# VALVEBOARD_ValveDrive1.net
KiCad netlist of a schematic drawn in Altium Designer
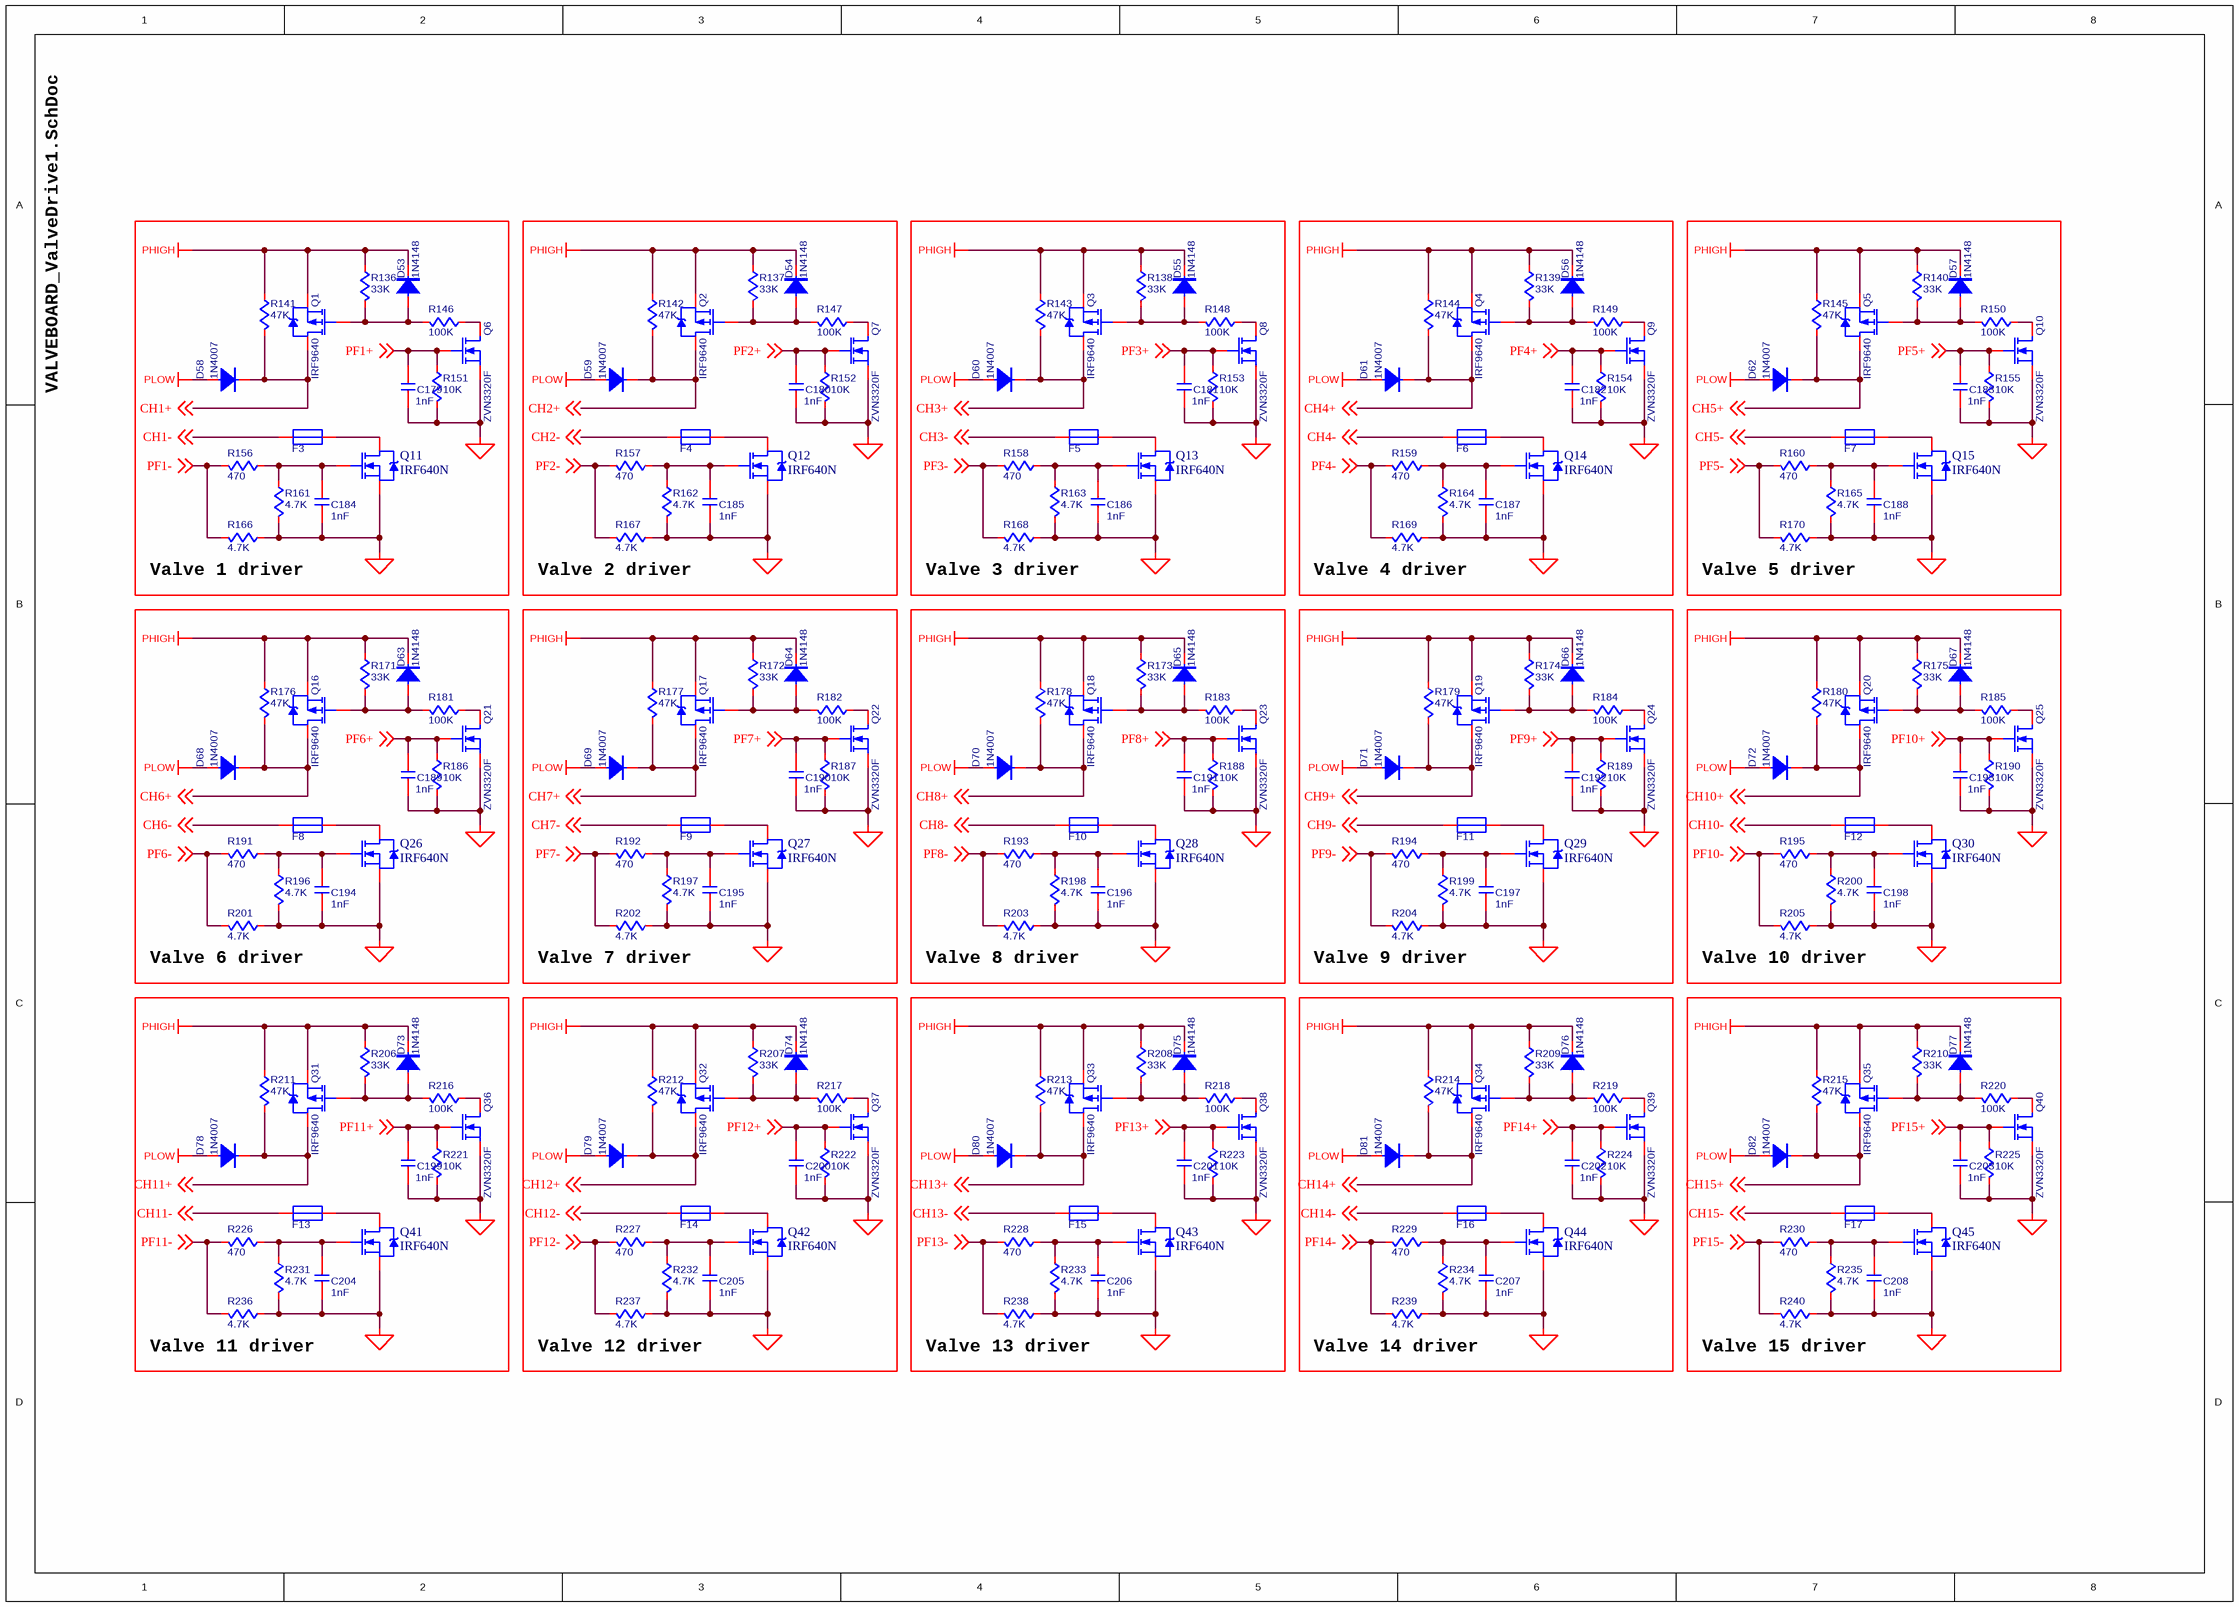
[diagram p0: VALVEBOARD_ValveDrive1.SchDoc]

(export (version "E")
  (design (tool "Eeschema 10.0.6"))
  (components
    (comp (ref "C179")
      (value "1nF")
      (footprint "zynq:C0603")
      (fields (field (name "VOLTAGE") "25V") (field (name "Comment") "C-NOMO"))
      (libsource (lib "zynq") (part "C-NOMO"))
    )
    (comp (ref "C180")
      (value "1nF")
      (footprint "zynq:C0603")
      (fields (field (name "VOLTAGE") "25V") (field (name "Comment") "C-NOMO"))
      (libsource (lib "zynq") (part "C-NOMO"))
    )
    (comp (ref "C181")
      (value "1nF")
      (footprint "zynq:C0603")
      (fields (field (name "VOLTAGE") "25V") (field (name "Comment") "C-NOMO"))
      (libsource (lib "zynq") (part "C-NOMO"))
    )
    (comp (ref "C182")
      (value "1nF")
      (footprint "zynq:C0603")
      (fields (field (name "VOLTAGE") "25V") (field (name "Comment") "C-NOMO"))
      (libsource (lib "zynq") (part "C-NOMO"))
    )
    (comp (ref "C183")
      (value "1nF")
      (footprint "zynq:C0603")
      (fields (field (name "VOLTAGE") "25V") (field (name "Comment") "C-NOMO"))
      (libsource (lib "zynq") (part "C-NOMO"))
    )
    (comp (ref "C184")
      (value "1nF")
      (footprint "zynq:C0603")
      (fields (field (name "VOLTAGE") "25V") (field (name "Comment") "C-NOMO"))
      (libsource (lib "zynq") (part "C-NOMO"))
    )
    (comp (ref "C185")
      (value "1nF")
      (footprint "zynq:C0603")
      (fields (field (name "VOLTAGE") "25V") (field (name "Comment") "C-NOMO"))
      (libsource (lib "zynq") (part "C-NOMO"))
    )
    (comp (ref "C186")
      (value "1nF")
      (footprint "zynq:C0603")
      (fields (field (name "VOLTAGE") "25V") (field (name "Comment") "C-NOMO"))
      (libsource (lib "zynq") (part "C-NOMO"))
    )
    (comp (ref "C187")
      (value "1nF")
      (footprint "zynq:C0603")
      (fields (field (name "VOLTAGE") "25V") (field (name "Comment") "C-NOMO"))
      (libsource (lib "zynq") (part "C-NOMO"))
    )
    (comp (ref "C188")
      (value "1nF")
      (footprint "zynq:C0603")
      (fields (field (name "VOLTAGE") "25V") (field (name "Comment") "C-NOMO"))
      (libsource (lib "zynq") (part "C-NOMO"))
    )
    (comp (ref "C189")
      (value "1nF")
      (footprint "zynq:C0603")
      (fields (field (name "VOLTAGE") "25V") (field (name "Comment") "C-NOMO"))
      (libsource (lib "zynq") (part "C-NOMO"))
    )
    (comp (ref "C190")
      (value "1nF")
      (footprint "zynq:C0603")
      (fields (field (name "VOLTAGE") "25V") (field (name "Comment") "C-NOMO"))
      (libsource (lib "zynq") (part "C-NOMO"))
    )
    (comp (ref "C191")
      (value "1nF")
      (footprint "zynq:C0603")
      (fields (field (name "VOLTAGE") "25V") (field (name "Comment") "C-NOMO"))
      (libsource (lib "zynq") (part "C-NOMO"))
    )
    (comp (ref "C192")
      (value "1nF")
      (footprint "zynq:C0603")
      (fields (field (name "VOLTAGE") "25V") (field (name "Comment") "C-NOMO"))
      (libsource (lib "zynq") (part "C-NOMO"))
    )
    (comp (ref "C193")
      (value "1nF")
      (footprint "zynq:C0603")
      (fields (field (name "VOLTAGE") "25V") (field (name "Comment") "C-NOMO"))
      (libsource (lib "zynq") (part "C-NOMO"))
    )
    (comp (ref "C194")
      (value "1nF")
      (footprint "zynq:C0603")
      (fields (field (name "VOLTAGE") "25V") (field (name "Comment") "C-NOMO"))
      (libsource (lib "zynq") (part "C-NOMO"))
    )
    (comp (ref "C195")
      (value "1nF")
      (footprint "zynq:C0603")
      (fields (field (name "VOLTAGE") "25V") (field (name "Comment") "C-NOMO"))
      (libsource (lib "zynq") (part "C-NOMO"))
    )
    (comp (ref "C196")
      (value "1nF")
      (footprint "zynq:C0603")
      (fields (field (name "VOLTAGE") "25V") (field (name "Comment") "C-NOMO"))
      (libsource (lib "zynq") (part "C-NOMO"))
    )
    (comp (ref "C197")
      (value "1nF")
      (footprint "zynq:C0603")
      (fields (field (name "VOLTAGE") "25V") (field (name "Comment") "C-NOMO"))
      (libsource (lib "zynq") (part "C-NOMO"))
    )
    (comp (ref "C198")
      (value "1nF")
      (footprint "zynq:C0603")
      (fields (field (name "VOLTAGE") "25V") (field (name "Comment") "C-NOMO"))
      (libsource (lib "zynq") (part "C-NOMO"))
    )
    (comp (ref "C199")
      (value "1nF")
      (footprint "zynq:C0603")
      (fields (field (name "VOLTAGE") "25V") (field (name "Comment") "C-NOMO"))
      (libsource (lib "zynq") (part "C-NOMO"))
    )
    (comp (ref "C200")
      (value "1nF")
      (footprint "zynq:C0603")
      (fields (field (name "VOLTAGE") "25V") (field (name "Comment") "C-NOMO"))
      (libsource (lib "zynq") (part "C-NOMO"))
    )
    (comp (ref "C201")
      (value "1nF")
      (footprint "zynq:C0603")
      (fields (field (name "VOLTAGE") "25V") (field (name "Comment") "C-NOMO"))
      (libsource (lib "zynq") (part "C-NOMO"))
    )
    (comp (ref "C202")
      (value "1nF")
      (footprint "zynq:C0603")
      (fields (field (name "VOLTAGE") "25V") (field (name "Comment") "C-NOMO"))
      (libsource (lib "zynq") (part "C-NOMO"))
    )
    (comp (ref "C203")
      (value "1nF")
      (footprint "zynq:C0603")
      (fields (field (name "VOLTAGE") "25V") (field (name "Comment") "C-NOMO"))
      (libsource (lib "zynq") (part "C-NOMO"))
    )
    (comp (ref "C204")
      (value "1nF")
      (footprint "zynq:C0603")
      (fields (field (name "VOLTAGE") "25V") (field (name "Comment") "C-NOMO"))
      (libsource (lib "zynq") (part "C-NOMO"))
    )
    (comp (ref "C205")
      (value "1nF")
      (footprint "zynq:C0603")
      (fields (field (name "VOLTAGE") "25V") (field (name "Comment") "C-NOMO"))
      (libsource (lib "zynq") (part "C-NOMO"))
    )
    (comp (ref "C206")
      (value "1nF")
      (footprint "zynq:C0603")
      (fields (field (name "VOLTAGE") "25V") (field (name "Comment") "C-NOMO"))
      (libsource (lib "zynq") (part "C-NOMO"))
    )
    (comp (ref "C207")
      (value "1nF")
      (footprint "zynq:C0603")
      (fields (field (name "VOLTAGE") "25V") (field (name "Comment") "C-NOMO"))
      (libsource (lib "zynq") (part "C-NOMO"))
    )
    (comp (ref "C208")
      (value "1nF")
      (footprint "zynq:C0603")
      (fields (field (name "VOLTAGE") "25V") (field (name "Comment") "C-NOMO"))
      (libsource (lib "zynq") (part "C-NOMO"))
    )
    (comp (ref "D53") (value "1N4148") (footprint "sod-123") (libsource (lib "zynq") (part "DIOD1")))
    (comp (ref "D54") (value "1N4148") (footprint "sod-123") (libsource (lib "zynq") (part "DIOD1")))
    (comp (ref "D55") (value "1N4148") (footprint "sod-123") (libsource (lib "zynq") (part "DIOD1")))
    (comp (ref "D56") (value "1N4148") (footprint "sod-123") (libsource (lib "zynq") (part "DIOD1")))
    (comp (ref "D57") (value "1N4148") (footprint "sod-123") (libsource (lib "zynq") (part "DIOD1")))
    (comp (ref "D58") (value "1N4007") (footprint "zynq:1N4148") (libsource (lib "") (part "DIOD1_1")))
    (comp (ref "D59") (value "1N4007") (footprint "zynq:1N4148") (libsource (lib "") (part "DIOD1_1")))
    (comp (ref "D60") (value "1N4007") (footprint "zynq:1N4148") (libsource (lib "") (part "DIOD1_1")))
    (comp (ref "D61") (value "1N4007") (footprint "zynq:1N4148") (libsource (lib "") (part "DIOD1_1")))
    (comp (ref "D62") (value "1N4007") (footprint "zynq:1N4148") (libsource (lib "") (part "DIOD1_1")))
    (comp (ref "D63") (value "1N4148") (footprint "sod-123") (libsource (lib "zynq") (part "DIOD1")))
    (comp (ref "D64") (value "1N4148") (footprint "sod-123") (libsource (lib "zynq") (part "DIOD1")))
    (comp (ref "D65") (value "1N4148") (footprint "sod-123") (libsource (lib "zynq") (part "DIOD1")))
    (comp (ref "D66") (value "1N4148") (footprint "sod-123") (libsource (lib "zynq") (part "DIOD1")))
    (comp (ref "D67") (value "1N4148") (footprint "sod-123") (libsource (lib "zynq") (part "DIOD1")))
    (comp (ref "D68") (value "1N4007") (footprint "zynq:1N4148") (libsource (lib "") (part "DIOD1_1")))
    (comp (ref "D69") (value "1N4007") (footprint "zynq:1N4148") (libsource (lib "") (part "DIOD1_1")))
    (comp (ref "D70") (value "1N4007") (footprint "zynq:1N4148") (libsource (lib "") (part "DIOD1_1")))
    (comp (ref "D71") (value "1N4007") (footprint "zynq:1N4148") (libsource (lib "") (part "DIOD1_1")))
    (comp (ref "D72") (value "1N4007") (footprint "zynq:1N4148") (libsource (lib "") (part "DIOD1_1")))
    (comp (ref "D73") (value "1N4148") (footprint "sod-123") (libsource (lib "zynq") (part "DIOD1")))
    (comp (ref "D74") (value "1N4148") (footprint "sod-123") (libsource (lib "zynq") (part "DIOD1")))
    (comp (ref "D75") (value "1N4148") (footprint "sod-123") (libsource (lib "zynq") (part "DIOD1")))
    (comp (ref "D76") (value "1N4148") (footprint "sod-123") (libsource (lib "zynq") (part "DIOD1")))
    (comp (ref "D77") (value "1N4148") (footprint "sod-123") (libsource (lib "zynq") (part "DIOD1")))
    (comp (ref "D78") (value "1N4007") (footprint "zynq:1N4148") (libsource (lib "") (part "DIOD1_1")))
    (comp (ref "D79") (value "1N4007") (footprint "zynq:1N4148") (libsource (lib "") (part "DIOD1_1")))
    (comp (ref "D80") (value "1N4007") (footprint "zynq:1N4148") (libsource (lib "") (part "DIOD1_1")))
    (comp (ref "D81") (value "1N4007") (footprint "zynq:1N4148") (libsource (lib "") (part "DIOD1_1")))
    (comp (ref "D82") (value "1N4007") (footprint "zynq:1N4148") (libsource (lib "") (part "DIOD1_1")))
    (comp (ref "F3") (value "F50") (footprint "zynq:F-TH") (libsource (lib "zynq") (part "F50")))
    (comp (ref "F4") (value "F50") (footprint "zynq:F-TH") (libsource (lib "zynq") (part "F50")))
    (comp (ref "F5") (value "F50") (footprint "zynq:F-TH") (libsource (lib "zynq") (part "F50")))
    (comp (ref "F6") (value "F50") (footprint "zynq:F-TH") (libsource (lib "zynq") (part "F50")))
    (comp (ref "F7") (value "F50") (footprint "zynq:F-TH") (libsource (lib "zynq") (part "F50")))
    (comp (ref "F8") (value "F50") (footprint "zynq:F-TH") (libsource (lib "zynq") (part "F50")))
    (comp (ref "F9") (value "F50") (footprint "zynq:F-TH") (libsource (lib "zynq") (part "F50")))
    (comp (ref "F10") (value "F50") (footprint "zynq:F-TH") (libsource (lib "zynq") (part "F50")))
    (comp (ref "F11") (value "F50") (footprint "zynq:F-TH") (libsource (lib "zynq") (part "F50")))
    (comp (ref "F12") (value "F50") (footprint "zynq:F-TH") (libsource (lib "zynq") (part "F50")))
    (comp (ref "F13") (value "F50") (footprint "zynq:F-TH") (libsource (lib "zynq") (part "F50")))
    (comp (ref "F14") (value "F50") (footprint "zynq:F-TH") (libsource (lib "zynq") (part "F50")))
    (comp (ref "F15") (value "F50") (footprint "zynq:F-TH") (libsource (lib "zynq") (part "F50")))
    (comp (ref "F16") (value "F50") (footprint "zynq:F-TH") (libsource (lib "zynq") (part "F50")))
    (comp (ref "F17") (value "F50") (footprint "zynq:F-TH") (libsource (lib "zynq") (part "F50")))
    (comp (ref "Q1")
      (value "IRF9640")
      (footprint "TO-220AB")
      (description "P-Channel Power MOSFET")
      (fields (field (name "PUBLISHER") "Altium Limited"))
      (libsource (lib "zynq") (part "IRF9640"))
    )
    (comp (ref "Q2")
      (value "IRF9640")
      (footprint "TO-220AB")
      (description "P-Channel Power MOSFET")
      (fields (field (name "PUBLISHER") "Altium Limited"))
      (libsource (lib "zynq") (part "IRF9640"))
    )
    (comp (ref "Q3")
      (value "IRF9640")
      (footprint "TO-220AB")
      (description "P-Channel Power MOSFET")
      (fields (field (name "PUBLISHER") "Altium Limited"))
      (libsource (lib "zynq") (part "IRF9640"))
    )
    (comp (ref "Q4")
      (value "IRF9640")
      (footprint "TO-220AB")
      (description "P-Channel Power MOSFET")
      (fields (field (name "PUBLISHER") "Altium Limited"))
      (libsource (lib "zynq") (part "IRF9640"))
    )
    (comp (ref "Q5")
      (value "IRF9640")
      (footprint "TO-220AB")
      (description "P-Channel Power MOSFET")
      (fields (field (name "PUBLISHER") "Altium Limited"))
      (libsource (lib "zynq") (part "IRF9640"))
    )
    (comp (ref "Q6")
      (value "ZVN3320F")
      (footprint "zynq:ZVN3320F")
      (description "N-Channel MOSFET")
      (fields (field (name "PUBLISHER") "Altium Limited"))
      (libsource (lib "zynq") (part "ZVN3320F"))
    )
    (comp (ref "Q7")
      (value "ZVN3320F")
      (footprint "zynq:ZVN3320F")
      (description "N-Channel MOSFET")
      (fields (field (name "PUBLISHER") "Altium Limited"))
      (libsource (lib "zynq") (part "ZVN3320F"))
    )
    (comp (ref "Q8")
      (value "ZVN3320F")
      (footprint "zynq:ZVN3320F")
      (description "N-Channel MOSFET")
      (fields (field (name "PUBLISHER") "Altium Limited"))
      (libsource (lib "zynq") (part "ZVN3320F"))
    )
    (comp (ref "Q9")
      (value "ZVN3320F")
      (footprint "zynq:ZVN3320F")
      (description "N-Channel MOSFET")
      (fields (field (name "PUBLISHER") "Altium Limited"))
      (libsource (lib "zynq") (part "ZVN3320F"))
    )
    (comp (ref "Q10")
      (value "ZVN3320F")
      (footprint "zynq:ZVN3320F")
      (description "N-Channel MOSFET")
      (fields (field (name "PUBLISHER") "Altium Limited"))
      (libsource (lib "zynq") (part "ZVN3320F"))
    )
    (comp (ref "Q11")
      (value "IRF640N")
      (footprint "zynq:TO-220AB")
      (description "N-Channel Power MOSFET")
      (fields (field (name "PUBLISHER") "Altium Limited"))
      (libsource (lib "zynq") (part "IRF640N"))
    )
    (comp (ref "Q12")
      (value "IRF640N")
      (footprint "zynq:TO-220AB")
      (description "N-Channel Power MOSFET")
      (fields (field (name "PUBLISHER") "Altium Limited"))
      (libsource (lib "zynq") (part "IRF640N"))
    )
    (comp (ref "Q13")
      (value "IRF640N")
      (footprint "zynq:TO-220AB")
      (description "N-Channel Power MOSFET")
      (fields (field (name "PUBLISHER") "Altium Limited"))
      (libsource (lib "zynq") (part "IRF640N"))
    )
    (comp (ref "Q14")
      (value "IRF640N")
      (footprint "zynq:TO-220AB")
      (description "N-Channel Power MOSFET")
      (fields (field (name "PUBLISHER") "Altium Limited"))
      (libsource (lib "zynq") (part "IRF640N"))
    )
    (comp (ref "Q15")
      (value "IRF640N")
      (footprint "zynq:TO-220AB")
      (description "N-Channel Power MOSFET")
      (fields (field (name "PUBLISHER") "Altium Limited"))
      (libsource (lib "zynq") (part "IRF640N"))
    )
    (comp (ref "Q16")
      (value "IRF9640")
      (footprint "TO-220AB")
      (description "P-Channel Power MOSFET")
      (fields (field (name "PUBLISHER") "Altium Limited"))
      (libsource (lib "zynq") (part "IRF9640"))
    )
    (comp (ref "Q17")
      (value "IRF9640")
      (footprint "TO-220AB")
      (description "P-Channel Power MOSFET")
      (fields (field (name "PUBLISHER") "Altium Limited"))
      (libsource (lib "zynq") (part "IRF9640"))
    )
    (comp (ref "Q18")
      (value "IRF9640")
      (footprint "TO-220AB")
      (description "P-Channel Power MOSFET")
      (fields (field (name "PUBLISHER") "Altium Limited"))
      (libsource (lib "zynq") (part "IRF9640"))
    )
    (comp (ref "Q19")
      (value "IRF9640")
      (footprint "TO-220AB")
      (description "P-Channel Power MOSFET")
      (fields (field (name "PUBLISHER") "Altium Limited"))
      (libsource (lib "zynq") (part "IRF9640"))
    )
    (comp (ref "Q20")
      (value "IRF9640")
      (footprint "TO-220AB")
      (description "P-Channel Power MOSFET")
      (fields (field (name "PUBLISHER") "Altium Limited"))
      (libsource (lib "zynq") (part "IRF9640"))
    )
    (comp (ref "Q21")
      (value "ZVN3320F")
      (footprint "zynq:ZVN3320F")
      (description "N-Channel MOSFET")
      (fields (field (name "PUBLISHER") "Altium Limited"))
      (libsource (lib "zynq") (part "ZVN3320F"))
    )
    (comp (ref "Q22")
      (value "ZVN3320F")
      (footprint "zynq:ZVN3320F")
      (description "N-Channel MOSFET")
      (fields (field (name "PUBLISHER") "Altium Limited"))
      (libsource (lib "zynq") (part "ZVN3320F"))
    )
    (comp (ref "Q23")
      (value "ZVN3320F")
      (footprint "zynq:ZVN3320F")
      (description "N-Channel MOSFET")
      (fields (field (name "PUBLISHER") "Altium Limited"))
      (libsource (lib "zynq") (part "ZVN3320F"))
    )
    (comp (ref "Q24")
      (value "ZVN3320F")
      (footprint "zynq:ZVN3320F")
      (description "N-Channel MOSFET")
      (fields (field (name "PUBLISHER") "Altium Limited"))
      (libsource (lib "zynq") (part "ZVN3320F"))
    )
    (comp (ref "Q25")
      (value "ZVN3320F")
      (footprint "zynq:ZVN3320F")
      (description "N-Channel MOSFET")
      (fields (field (name "PUBLISHER") "Altium Limited"))
      (libsource (lib "zynq") (part "ZVN3320F"))
    )
    (comp (ref "Q26")
      (value "IRF640N")
      (footprint "zynq:TO-220AB")
      (description "N-Channel Power MOSFET")
      (fields (field (name "PUBLISHER") "Altium Limited"))
      (libsource (lib "zynq") (part "IRF640N"))
    )
    (comp (ref "Q27")
      (value "IRF640N")
      (footprint "zynq:TO-220AB")
      (description "N-Channel Power MOSFET")
      (fields (field (name "PUBLISHER") "Altium Limited"))
      (libsource (lib "zynq") (part "IRF640N"))
    )
    (comp (ref "Q28")
      (value "IRF640N")
      (footprint "zynq:TO-220AB")
      (description "N-Channel Power MOSFET")
      (fields (field (name "PUBLISHER") "Altium Limited"))
      (libsource (lib "zynq") (part "IRF640N"))
    )
    (comp (ref "Q29")
      (value "IRF640N")
      (footprint "zynq:TO-220AB")
      (description "N-Channel Power MOSFET")
      (fields (field (name "PUBLISHER") "Altium Limited"))
      (libsource (lib "zynq") (part "IRF640N"))
    )
    (comp (ref "Q30")
      (value "IRF640N")
      (footprint "zynq:TO-220AB")
      (description "N-Channel Power MOSFET")
      (fields (field (name "PUBLISHER") "Altium Limited"))
      (libsource (lib "zynq") (part "IRF640N"))
    )
    (comp (ref "Q31")
      (value "IRF9640")
      (footprint "TO-220AB")
      (description "P-Channel Power MOSFET")
      (fields (field (name "PUBLISHER") "Altium Limited"))
      (libsource (lib "zynq") (part "IRF9640"))
    )
    (comp (ref "Q32")
      (value "IRF9640")
      (footprint "TO-220AB")
      (description "P-Channel Power MOSFET")
      (fields (field (name "PUBLISHER") "Altium Limited"))
      (libsource (lib "zynq") (part "IRF9640"))
    )
    (comp (ref "Q33")
      (value "IRF9640")
      (footprint "TO-220AB")
      (description "P-Channel Power MOSFET")
      (fields (field (name "PUBLISHER") "Altium Limited"))
      (libsource (lib "zynq") (part "IRF9640"))
    )
    (comp (ref "Q34")
      (value "IRF9640")
      (footprint "TO-220AB")
      (description "P-Channel Power MOSFET")
      (fields (field (name "PUBLISHER") "Altium Limited"))
      (libsource (lib "zynq") (part "IRF9640"))
    )
    (comp (ref "Q35")
      (value "IRF9640")
      (footprint "TO-220AB")
      (description "P-Channel Power MOSFET")
      (fields (field (name "PUBLISHER") "Altium Limited"))
      (libsource (lib "zynq") (part "IRF9640"))
    )
    (comp (ref "Q36")
      (value "ZVN3320F")
      (footprint "zynq:ZVN3320F")
      (description "N-Channel MOSFET")
      (fields (field (name "PUBLISHER") "Altium Limited"))
      (libsource (lib "zynq") (part "ZVN3320F"))
    )
    (comp (ref "Q37")
      (value "ZVN3320F")
      (footprint "zynq:ZVN3320F")
      (description "N-Channel MOSFET")
      (fields (field (name "PUBLISHER") "Altium Limited"))
      (libsource (lib "zynq") (part "ZVN3320F"))
    )
    (comp (ref "Q38")
      (value "ZVN3320F")
      (footprint "zynq:ZVN3320F")
      (description "N-Channel MOSFET")
      (fields (field (name "PUBLISHER") "Altium Limited"))
      (libsource (lib "zynq") (part "ZVN3320F"))
    )
    (comp (ref "Q39")
      (value "ZVN3320F")
      (footprint "zynq:ZVN3320F")
      (description "N-Channel MOSFET")
      (fields (field (name "PUBLISHER") "Altium Limited"))
      (libsource (lib "zynq") (part "ZVN3320F"))
    )
    (comp (ref "Q40")
      (value "ZVN3320F")
      (footprint "zynq:ZVN3320F")
      (description "N-Channel MOSFET")
      (fields (field (name "PUBLISHER") "Altium Limited"))
      (libsource (lib "zynq") (part "ZVN3320F"))
    )
    (comp (ref "Q41")
      (value "IRF640N")
      (footprint "zynq:TO-220AB")
      (description "N-Channel Power MOSFET")
      (fields (field (name "PUBLISHER") "Altium Limited"))
      (libsource (lib "zynq") (part "IRF640N"))
    )
    (comp (ref "Q42")
      (value "IRF640N")
      (footprint "zynq:TO-220AB")
      (description "N-Channel Power MOSFET")
      (fields (field (name "PUBLISHER") "Altium Limited"))
      (libsource (lib "zynq") (part "IRF640N"))
    )
    (comp (ref "Q43")
      (value "IRF640N")
      (footprint "zynq:TO-220AB")
      (description "N-Channel Power MOSFET")
      (fields (field (name "PUBLISHER") "Altium Limited"))
      (libsource (lib "zynq") (part "IRF640N"))
    )
    (comp (ref "Q44")
      (value "IRF640N")
      (footprint "zynq:TO-220AB")
      (description "N-Channel Power MOSFET")
      (fields (field (name "PUBLISHER") "Altium Limited"))
      (libsource (lib "zynq") (part "IRF640N"))
    )
    (comp (ref "Q45")
      (value "IRF640N")
      (footprint "zynq:TO-220AB")
      (description "N-Channel Power MOSFET")
      (fields (field (name "PUBLISHER") "Altium Limited"))
      (libsource (lib "zynq") (part "IRF640N"))
    )
    (comp (ref "R136")
      (value "33K")
      (footprint "zynq:R0603")
      (fields (field (name "Comment") "R"))
      (libsource (lib "zynq") (part "R"))
    )
    (comp (ref "R137")
      (value "33K")
      (footprint "zynq:R0603")
      (fields (field (name "Comment") "R"))
      (libsource (lib "zynq") (part "R"))
    )
    (comp (ref "R138")
      (value "33K")
      (footprint "zynq:R0603")
      (fields (field (name "Comment") "R"))
      (libsource (lib "zynq") (part "R"))
    )
    (comp (ref "R139")
      (value "33K")
      (footprint "zynq:R0603")
      (fields (field (name "Comment") "R"))
      (libsource (lib "zynq") (part "R"))
    )
    (comp (ref "R140")
      (value "33K")
      (footprint "zynq:R0603")
      (fields (field (name "Comment") "R"))
      (libsource (lib "zynq") (part "R"))
    )
    (comp (ref "R141")
      (value "47K")
      (footprint "R2512")
      (fields (field (name "Comment") "R"))
      (libsource (lib "zynq") (part "R"))
    )
    (comp (ref "R142")
      (value "47K")
      (footprint "R2512")
      (fields (field (name "Comment") "R"))
      (libsource (lib "zynq") (part "R"))
    )
    (comp (ref "R143")
      (value "47K")
      (footprint "R2512")
      (fields (field (name "Comment") "R"))
      (libsource (lib "zynq") (part "R"))
    )
    (comp (ref "R144")
      (value "47K")
      (footprint "R2512")
      (fields (field (name "Comment") "R"))
      (libsource (lib "zynq") (part "R"))
    )
    (comp (ref "R145")
      (value "47K")
      (footprint "R2512")
      (fields (field (name "Comment") "R"))
      (libsource (lib "zynq") (part "R"))
    )
    (comp (ref "R146")
      (value "100K")
      (footprint "zynq:R0603")
      (fields (field (name "Comment") "R"))
      (libsource (lib "zynq") (part "R"))
    )
    (comp (ref "R147")
      (value "100K")
      (footprint "zynq:R0603")
      (fields (field (name "Comment") "R"))
      (libsource (lib "zynq") (part "R"))
    )
    (comp (ref "R148")
      (value "100K")
      (footprint "zynq:R0603")
      (fields (field (name "Comment") "R"))
      (libsource (lib "zynq") (part "R"))
    )
    (comp (ref "R149")
      (value "100K")
      (footprint "zynq:R0603")
      (fields (field (name "Comment") "R"))
      (libsource (lib "zynq") (part "R"))
    )
    (comp (ref "R150")
      (value "100K")
      (footprint "zynq:R0603")
      (fields (field (name "Comment") "R"))
      (libsource (lib "zynq") (part "R"))
    )
    (comp (ref "R151")
      (value "10K")
      (footprint "zynq:R0603")
      (fields (field (name "Comment") "R"))
      (libsource (lib "zynq") (part "R"))
    )
    (comp (ref "R152")
      (value "10K")
      (footprint "zynq:R0603")
      (fields (field (name "Comment") "R"))
      (libsource (lib "zynq") (part "R"))
    )
    (comp (ref "R153")
      (value "10K")
      (footprint "zynq:R0603")
      (fields (field (name "Comment") "R"))
      (libsource (lib "zynq") (part "R"))
    )
    (comp (ref "R154")
      (value "10K")
      (footprint "zynq:R0603")
      (fields (field (name "Comment") "R"))
      (libsource (lib "zynq") (part "R"))
    )
    (comp (ref "R155")
      (value "10K")
      (footprint "zynq:R0603")
      (fields (field (name "Comment") "R"))
      (libsource (lib "zynq") (part "R"))
    )
    (comp (ref "R156")
      (value "470")
      (footprint "zynq:R0402")
      (fields (field (name "Comment") "R"))
      (libsource (lib "zynq") (part "R"))
    )
    (comp (ref "R157")
      (value "470")
      (footprint "zynq:R0402")
      (fields (field (name "Comment") "R"))
      (libsource (lib "zynq") (part "R"))
    )
    (comp (ref "R158")
      (value "470")
      (footprint "zynq:R0402")
      (fields (field (name "Comment") "R"))
      (libsource (lib "zynq") (part "R"))
    )
    (comp (ref "R159")
      (value "470")
      (footprint "zynq:R0402")
      (fields (field (name "Comment") "R"))
      (libsource (lib "zynq") (part "R"))
    )
    (comp (ref "R160")
      (value "470")
      (footprint "zynq:R0402")
      (fields (field (name "Comment") "R"))
      (libsource (lib "zynq") (part "R"))
    )
    (comp (ref "R161")
      (value "4.7K")
      (footprint "zynq:R0402")
      (fields (field (name "Comment") "R"))
      (libsource (lib "zynq") (part "R"))
    )
    (comp (ref "R162")
      (value "4.7K")
      (footprint "zynq:R0402")
      (fields (field (name "Comment") "R"))
      (libsource (lib "zynq") (part "R"))
    )
    (comp (ref "R163")
      (value "4.7K")
      (footprint "zynq:R0402")
      (fields (field (name "Comment") "R"))
      (libsource (lib "zynq") (part "R"))
    )
    (comp (ref "R164")
      (value "4.7K")
      (footprint "zynq:R0402")
      (fields (field (name "Comment") "R"))
      (libsource (lib "zynq") (part "R"))
    )
    (comp (ref "R165")
      (value "4.7K")
      (footprint "zynq:R0402")
      (fields (field (name "Comment") "R"))
      (libsource (lib "zynq") (part "R"))
    )
    (comp (ref "R166")
      (value "4.7K")
      (footprint "zynq:R0402")
      (fields (field (name "Comment") "R"))
      (libsource (lib "zynq") (part "R"))
    )
    (comp (ref "R167")
      (value "4.7K")
      (footprint "zynq:R0402")
      (fields (field (name "Comment") "R"))
      (libsource (lib "zynq") (part "R"))
    )
    (comp (ref "R168")
      (value "4.7K")
      (footprint "zynq:R0402")
      (fields (field (name "Comment") "R"))
      (libsource (lib "zynq") (part "R"))
    )
    (comp (ref "R169")
      (value "4.7K")
      (footprint "zynq:R0402")
      (fields (field (name "Comment") "R"))
      (libsource (lib "zynq") (part "R"))
    )
    (comp (ref "R170")
      (value "4.7K")
      (footprint "zynq:R0402")
      (fields (field (name "Comment") "R"))
      (libsource (lib "zynq") (part "R"))
    )
    (comp (ref "R171")
      (value "33K")
      (footprint "zynq:R0603")
      (fields (field (name "Comment") "R"))
      (libsource (lib "zynq") (part "R"))
    )
    (comp (ref "R172")
      (value "33K")
      (footprint "zynq:R0603")
      (fields (field (name "Comment") "R"))
      (libsource (lib "zynq") (part "R"))
    )
    (comp (ref "R173")
      (value "33K")
      (footprint "zynq:R0603")
      (fields (field (name "Comment") "R"))
      (libsource (lib "zynq") (part "R"))
    )
    (comp (ref "R174")
      (value "33K")
      (footprint "zynq:R0603")
      (fields (field (name "Comment") "R"))
      (libsource (lib "zynq") (part "R"))
    )
    (comp (ref "R175")
      (value "33K")
      (footprint "zynq:R0603")
      (fields (field (name "Comment") "R"))
      (libsource (lib "zynq") (part "R"))
    )
    (comp (ref "R176")
      (value "47K")
      (footprint "R2512")
      (fields (field (name "Comment") "R"))
      (libsource (lib "zynq") (part "R"))
    )
    (comp (ref "R177")
      (value "47K")
      (footprint "R2512")
      (fields (field (name "Comment") "R"))
      (libsource (lib "zynq") (part "R"))
    )
    (comp (ref "R178")
      (value "47K")
      (footprint "R2512")
      (fields (field (name "Comment") "R"))
      (libsource (lib "zynq") (part "R"))
    )
    (comp (ref "R179")
      (value "47K")
      (footprint "R2512")
      (fields (field (name "Comment") "R"))
      (libsource (lib "zynq") (part "R"))
    )
    (comp (ref "R180")
      (value "47K")
      (footprint "R2512")
      (fields (field (name "Comment") "R"))
      (libsource (lib "zynq") (part "R"))
    )
    (comp (ref "R181")
      (value "100K")
      (footprint "zynq:R0603")
      (fields (field (name "Comment") "R"))
      (libsource (lib "zynq") (part "R"))
    )
    (comp (ref "R182")
      (value "100K")
      (footprint "zynq:R0603")
      (fields (field (name "Comment") "R"))
      (libsource (lib "zynq") (part "R"))
    )
    (comp (ref "R183")
      (value "100K")
      (footprint "zynq:R0603")
      (fields (field (name "Comment") "R"))
      (libsource (lib "zynq") (part "R"))
    )
    (comp (ref "R184")
      (value "100K")
      (footprint "zynq:R0603")
      (fields (field (name "Comment") "R"))
      (libsource (lib "zynq") (part "R"))
    )
    (comp (ref "R185")
      (value "100K")
      (footprint "zynq:R0603")
      (fields (field (name "Comment") "R"))
      (libsource (lib "zynq") (part "R"))
    )
    (comp (ref "R186")
      (value "10K")
      (footprint "zynq:R0603")
      (fields (field (name "Comment") "R"))
      (libsource (lib "zynq") (part "R"))
    )
    (comp (ref "R187")
      (value "10K")
      (footprint "zynq:R0603")
      (fields (field (name "Comment") "R"))
      (libsource (lib "zynq") (part "R"))
    )
    (comp (ref "R188")
      (value "10K")
      (footprint "zynq:R0603")
      (fields (field (name "Comment") "R"))
      (libsource (lib "zynq") (part "R"))
    )
    (comp (ref "R189")
      (value "10K")
      (footprint "zynq:R0603")
      (fields (field (name "Comment") "R"))
      (libsource (lib "zynq") (part "R"))
    )
    (comp (ref "R190")
      (value "10K")
      (footprint "zynq:R0603")
      (fields (field (name "Comment") "R"))
      (libsource (lib "zynq") (part "R"))
    )
    (comp (ref "R191")
      (value "470")
      (footprint "zynq:R0402")
      (fields (field (name "Comment") "R"))
      (libsource (lib "zynq") (part "R"))
    )
    (comp (ref "R192")
      (value "470")
      (footprint "zynq:R0402")
      (fields (field (name "Comment") "R"))
      (libsource (lib "zynq") (part "R"))
    )
    (comp (ref "R193")
      (value "470")
      (footprint "zynq:R0402")
      (fields (field (name "Comment") "R"))
      (libsource (lib "zynq") (part "R"))
    )
    (comp (ref "R194")
      (value "470")
      (footprint "zynq:R0402")
      (fields (field (name "Comment") "R"))
      (libsource (lib "zynq") (part "R"))
    )
    (comp (ref "R195")
      (value "470")
      (footprint "zynq:R0402")
      (fields (field (name "Comment") "R"))
      (libsource (lib "zynq") (part "R"))
    )
    (comp (ref "R196")
      (value "4.7K")
      (footprint "zynq:R0402")
      (fields (field (name "Comment") "R"))
      (libsource (lib "zynq") (part "R"))
    )
    (comp (ref "R197")
      (value "4.7K")
      (footprint "zynq:R0402")
      (fields (field (name "Comment") "R"))
      (libsource (lib "zynq") (part "R"))
    )
    (comp (ref "R198")
      (value "4.7K")
      (footprint "zynq:R0402")
      (fields (field (name "Comment") "R"))
      (libsource (lib "zynq") (part "R"))
    )
    (comp (ref "R199")
      (value "4.7K")
      (footprint "zynq:R0402")
      (fields (field (name "Comment") "R"))
      (libsource (lib "zynq") (part "R"))
    )
    (comp (ref "R200")
      (value "4.7K")
      (footprint "zynq:R0402")
      (fields (field (name "Comment") "R"))
      (libsource (lib "zynq") (part "R"))
    )
    (comp (ref "R201")
      (value "4.7K")
      (footprint "zynq:R0402")
      (fields (field (name "Comment") "R"))
      (libsource (lib "zynq") (part "R"))
    )
    (comp (ref "R202")
      (value "4.7K")
      (footprint "zynq:R0402")
      (fields (field (name "Comment") "R"))
      (libsource (lib "zynq") (part "R"))
    )
    (comp (ref "R203")
      (value "4.7K")
      (footprint "zynq:R0402")
      (fields (field (name "Comment") "R"))
      (libsource (lib "zynq") (part "R"))
    )
    (comp (ref "R204")
      (value "4.7K")
      (footprint "zynq:R0402")
      (fields (field (name "Comment") "R"))
      (libsource (lib "zynq") (part "R"))
    )
    (comp (ref "R205")
      (value "4.7K")
      (footprint "zynq:R0402")
      (fields (field (name "Comment") "R"))
      (libsource (lib "zynq") (part "R"))
    )
    (comp (ref "R206")
      (value "33K")
      (footprint "zynq:R0603")
      (fields (field (name "Comment") "R"))
      (libsource (lib "zynq") (part "R"))
    )
    (comp (ref "R207")
      (value "33K")
      (footprint "zynq:R0603")
      (fields (field (name "Comment") "R"))
      (libsource (lib "zynq") (part "R"))
    )
    (comp (ref "R208")
      (value "33K")
      (footprint "zynq:R0603")
      (fields (field (name "Comment") "R"))
      (libsource (lib "zynq") (part "R"))
    )
    (comp (ref "R209")
      (value "33K")
      (footprint "zynq:R0603")
      (fields (field (name "Comment") "R"))
      (libsource (lib "zynq") (part "R"))
    )
    (comp (ref "R210")
      (value "33K")
      (footprint "zynq:R0603")
      (fields (field (name "Comment") "R"))
      (libsource (lib "zynq") (part "R"))
    )
    (comp (ref "R211")
      (value "47K")
      (footprint "R2512")
      (fields (field (name "Comment") "R"))
      (libsource (lib "zynq") (part "R"))
    )
    (comp (ref "R212")
      (value "47K")
      (footprint "R2512")
      (fields (field (name "Comment") "R"))
      (libsource (lib "zynq") (part "R"))
    )
    (comp (ref "R213")
      (value "47K")
      (footprint "R2512")
      (fields (field (name "Comment") "R"))
      (libsource (lib "zynq") (part "R"))
    )
    (comp (ref "R214")
      (value "47K")
      (footprint "R2512")
      (fields (field (name "Comment") "R"))
      (libsource (lib "zynq") (part "R"))
    )
    (comp (ref "R215")
      (value "47K")
      (footprint "R2512")
      (fields (field (name "Comment") "R"))
      (libsource (lib "zynq") (part "R"))
    )
    (comp (ref "R216")
      (value "100K")
      (footprint "zynq:R0603")
      (fields (field (name "Comment") "R"))
      (libsource (lib "zynq") (part "R"))
    )
    (comp (ref "R217")
      (value "100K")
      (footprint "zynq:R0603")
      (fields (field (name "Comment") "R"))
      (libsource (lib "zynq") (part "R"))
    )
    (comp (ref "R218")
      (value "100K")
      (footprint "zynq:R0603")
      (fields (field (name "Comment") "R"))
      (libsource (lib "zynq") (part "R"))
    )
    (comp (ref "R219")
      (value "100K")
      (footprint "zynq:R0603")
      (fields (field (name "Comment") "R"))
      (libsource (lib "zynq") (part "R"))
    )
    (comp (ref "R220")
      (value "100K")
      (footprint "zynq:R0603")
      (fields (field (name "Comment") "R"))
      (libsource (lib "zynq") (part "R"))
    )
    (comp (ref "R221")
      (value "10K")
      (footprint "zynq:R0603")
      (fields (field (name "Comment") "R"))
      (libsource (lib "zynq") (part "R"))
    )
    (comp (ref "R222")
      (value "10K")
      (footprint "zynq:R0603")
      (fields (field (name "Comment") "R"))
      (libsource (lib "zynq") (part "R"))
    )
    (comp (ref "R223")
      (value "10K")
      (footprint "zynq:R0603")
      (fields (field (name "Comment") "R"))
      (libsource (lib "zynq") (part "R"))
    )
    (comp (ref "R224")
      (value "10K")
      (footprint "zynq:R0603")
      (fields (field (name "Comment") "R"))
      (libsource (lib "zynq") (part "R"))
    )
    (comp (ref "R225")
      (value "10K")
      (footprint "zynq:R0603")
      (fields (field (name "Comment") "R"))
      (libsource (lib "zynq") (part "R"))
    )
    (comp (ref "R226")
      (value "470")
      (footprint "zynq:R0402")
      (fields (field (name "Comment") "R"))
      (libsource (lib "zynq") (part "R"))
    )
    (comp (ref "R227")
      (value "470")
      (footprint "zynq:R0402")
      (fields (field (name "Comment") "R"))
      (libsource (lib "zynq") (part "R"))
    )
    (comp (ref "R228")
      (value "470")
      (footprint "zynq:R0402")
      (fields (field (name "Comment") "R"))
      (libsource (lib "zynq") (part "R"))
    )
    (comp (ref "R229")
      (value "470")
      (footprint "zynq:R0402")
      (fields (field (name "Comment") "R"))
      (libsource (lib "zynq") (part "R"))
    )
    (comp (ref "R230")
      (value "470")
      (footprint "zynq:R0402")
      (fields (field (name "Comment") "R"))
      (libsource (lib "zynq") (part "R"))
    )
    (comp (ref "R231")
      (value "4.7K")
      (footprint "zynq:R0402")
      (fields (field (name "Comment") "R"))
      (libsource (lib "zynq") (part "R"))
    )
    (comp (ref "R232")
      (value "4.7K")
      (footprint "zynq:R0402")
      (fields (field (name "Comment") "R"))
      (libsource (lib "zynq") (part "R"))
    )
    (comp (ref "R233")
      (value "4.7K")
      (footprint "zynq:R0402")
      (fields (field (name "Comment") "R"))
      (libsource (lib "zynq") (part "R"))
    )
    (comp (ref "R234")
      (value "4.7K")
      (footprint "zynq:R0402")
      (fields (field (name "Comment") "R"))
      (libsource (lib "zynq") (part "R"))
    )
    (comp (ref "R235")
      (value "4.7K")
      (footprint "zynq:R0402")
      (fields (field (name "Comment") "R"))
      (libsource (lib "zynq") (part "R"))
    )
    (comp (ref "R236")
      (value "4.7K")
      (footprint "zynq:R0402")
      (fields (field (name "Comment") "R"))
      (libsource (lib "zynq") (part "R"))
    )
    (comp (ref "R237")
      (value "4.7K")
      (footprint "zynq:R0402")
      (fields (field (name "Comment") "R"))
      (libsource (lib "zynq") (part "R"))
    )
    (comp (ref "R238")
      (value "4.7K")
      (footprint "zynq:R0402")
      (fields (field (name "Comment") "R"))
      (libsource (lib "zynq") (part "R"))
    )
    (comp (ref "R239")
      (value "4.7K")
      (footprint "zynq:R0402")
      (fields (field (name "Comment") "R"))
      (libsource (lib "zynq") (part "R"))
    )
    (comp (ref "R240")
      (value "4.7K")
      (footprint "zynq:R0402")
      (fields (field (name "Comment") "R"))
      (libsource (lib "zynq") (part "R"))
    )
  )
  (nets
    (net (code "1") (name "CH1+") (class "Default")
      (node (ref "D58") (pin "1") (pinfunction "1_1") (pintype "passive"))
      (node (ref "Q1") (pin "2") (pinfunction "D_2") (pintype "passive"))
      (node (ref "R141") (pin "1") (pinfunction "1_1") (pintype "passive"))
    )
    (net (code "2") (name "CH1-") (class "Default") (node (ref "F3") (pin "1") (pintype "passive")))
    (net (code "3") (name "CH2+") (class "Default")
      (node (ref "D59") (pin "1") (pinfunction "1_1") (pintype "passive"))
      (node (ref "Q2") (pin "2") (pinfunction "D_2") (pintype "passive"))
      (node (ref "R142") (pin "1") (pinfunction "1_1") (pintype "passive"))
    )
    (net (code "4") (name "CH2-") (class "Default") (node (ref "F4") (pin "1") (pintype "passive")))
    (net (code "5") (name "CH3+") (class "Default")
      (node (ref "D60") (pin "1") (pinfunction "1_1") (pintype "passive"))
      (node (ref "Q3") (pin "2") (pinfunction "D_2") (pintype "passive"))
      (node (ref "R143") (pin "1") (pinfunction "1_1") (pintype "passive"))
    )
    (net (code "6") (name "CH3-") (class "Default") (node (ref "F5") (pin "1") (pintype "passive")))
    (net (code "7") (name "CH4+") (class "Default")
      (node (ref "D61") (pin "1") (pinfunction "1_1") (pintype "passive"))
      (node (ref "Q4") (pin "2") (pinfunction "D_2") (pintype "passive"))
      (node (ref "R144") (pin "1") (pinfunction "1_1") (pintype "passive"))
    )
    (net (code "8") (name "CH4-") (class "Default") (node (ref "F6") (pin "1") (pintype "passive")))
    (net (code "9") (name "CH5+") (class "Default")
      (node (ref "D62") (pin "1") (pinfunction "1_1") (pintype "passive"))
      (node (ref "Q5") (pin "2") (pinfunction "D_2") (pintype "passive"))
      (node (ref "R145") (pin "1") (pinfunction "1_1") (pintype "passive"))
    )
    (net (code "10") (name "CH5-") (class "Default") (node (ref "F7") (pin "1") (pintype "passive")))
    (net (code "11") (name "CH6+") (class "Default")
      (node (ref "D68") (pin "1") (pinfunction "1_1") (pintype "passive"))
      (node (ref "Q16") (pin "2") (pinfunction "D_2") (pintype "passive"))
      (node (ref "R176") (pin "1") (pinfunction "1_1") (pintype "passive"))
    )
    (net (code "12") (name "CH6-") (class "Default") (node (ref "F8") (pin "1") (pintype "passive")))
    (net (code "13") (name "CH7+") (class "Default")
      (node (ref "D69") (pin "1") (pinfunction "1_1") (pintype "passive"))
      (node (ref "Q17") (pin "2") (pinfunction "D_2") (pintype "passive"))
      (node (ref "R177") (pin "1") (pinfunction "1_1") (pintype "passive"))
    )
    (net (code "14") (name "CH7-") (class "Default") (node (ref "F9") (pin "1") (pintype "passive")))
    (net (code "15") (name "CH8+") (class "Default")
      (node (ref "D70") (pin "1") (pinfunction "1_1") (pintype "passive"))
      (node (ref "Q18") (pin "2") (pinfunction "D_2") (pintype "passive"))
      (node (ref "R178") (pin "1") (pinfunction "1_1") (pintype "passive"))
    )
    (net (code "16") (name "CH8-") (class "Default") (node (ref "F10") (pin "1") (pintype "passive")))
    (net (code "17") (name "CH9+") (class "Default")
      (node (ref "D71") (pin "1") (pinfunction "1_1") (pintype "passive"))
      (node (ref "Q19") (pin "2") (pinfunction "D_2") (pintype "passive"))
      (node (ref "R179") (pin "1") (pinfunction "1_1") (pintype "passive"))
    )
    (net (code "18") (name "CH9-") (class "Default") (node (ref "F11") (pin "1") (pintype "passive")))
    (net (code "19") (name "CH10+") (class "Default")
      (node (ref "D72") (pin "1") (pinfunction "1_1") (pintype "passive"))
      (node (ref "Q20") (pin "2") (pinfunction "D_2") (pintype "passive"))
      (node (ref "R180") (pin "1") (pinfunction "1_1") (pintype "passive"))
    )
    (net (code "20") (name "CH10-") (class "Default") (node (ref "F12") (pin "1") (pintype "passive")))
    (net (code "21") (name "CH11+") (class "Default")
      (node (ref "D78") (pin "1") (pinfunction "1_1") (pintype "passive"))
      (node (ref "Q31") (pin "2") (pinfunction "D_2") (pintype "passive"))
      (node (ref "R211") (pin "1") (pinfunction "1_1") (pintype "passive"))
    )
    (net (code "22") (name "CH11-") (class "Default") (node (ref "F13") (pin "1") (pintype "passive")))
    (net (code "23") (name "CH12+") (class "Default")
      (node (ref "D79") (pin "1") (pinfunction "1_1") (pintype "passive"))
      (node (ref "Q32") (pin "2") (pinfunction "D_2") (pintype "passive"))
      (node (ref "R212") (pin "1") (pinfunction "1_1") (pintype "passive"))
    )
    (net (code "24") (name "CH12-") (class "Default") (node (ref "F14") (pin "1") (pintype "passive")))
    (net (code "25") (name "CH13+") (class "Default")
      (node (ref "D80") (pin "1") (pinfunction "1_1") (pintype "passive"))
      (node (ref "Q33") (pin "2") (pinfunction "D_2") (pintype "passive"))
      (node (ref "R213") (pin "1") (pinfunction "1_1") (pintype "passive"))
    )
    (net (code "26") (name "CH13-") (class "Default") (node (ref "F15") (pin "1") (pintype "passive")))
    (net (code "27") (name "CH14+") (class "Default")
      (node (ref "D81") (pin "1") (pinfunction "1_1") (pintype "passive"))
      (node (ref "Q34") (pin "2") (pinfunction "D_2") (pintype "passive"))
      (node (ref "R214") (pin "1") (pinfunction "1_1") (pintype "passive"))
    )
    (net (code "28") (name "CH14-") (class "Default") (node (ref "F16") (pin "1") (pintype "passive")))
    (net (code "29") (name "CH15+") (class "Default")
      (node (ref "D82") (pin "1") (pinfunction "1_1") (pintype "passive"))
      (node (ref "Q35") (pin "2") (pinfunction "D_2") (pintype "passive"))
      (node (ref "R215") (pin "1") (pinfunction "1_1") (pintype "passive"))
    )
    (net (code "30") (name "CH15-") (class "Default") (node (ref "F17") (pin "1") (pintype "passive")))
    (net (code "31") (name "Net-(Q1-G)") (class "Default")
      (node (ref "D53") (pin "2") (pinfunction "2_2") (pintype "passive"))
      (node (ref "Q1") (pin "1") (pinfunction "G_1") (pintype "passive"))
      (node (ref "R136") (pin "1") (pinfunction "1_1") (pintype "passive"))
      (node (ref "R146") (pin "1") (pinfunction "1_1") (pintype "passive"))
    )
    (net (code "32") (name "Net-(Q2-G)") (class "Default")
      (node (ref "D54") (pin "2") (pinfunction "2_2") (pintype "passive"))
      (node (ref "Q2") (pin "1") (pinfunction "G_1") (pintype "passive"))
      (node (ref "R137") (pin "1") (pinfunction "1_1") (pintype "passive"))
      (node (ref "R147") (pin "1") (pinfunction "1_1") (pintype "passive"))
    )
    (net (code "33") (name "Net-(Q3-G)") (class "Default")
      (node (ref "D55") (pin "2") (pinfunction "2_2") (pintype "passive"))
      (node (ref "Q3") (pin "1") (pinfunction "G_1") (pintype "passive"))
      (node (ref "R138") (pin "1") (pinfunction "1_1") (pintype "passive"))
      (node (ref "R148") (pin "1") (pinfunction "1_1") (pintype "passive"))
    )
    (net (code "34") (name "Net-(Q4-G)") (class "Default")
      (node (ref "D56") (pin "2") (pinfunction "2_2") (pintype "passive"))
      (node (ref "Q4") (pin "1") (pinfunction "G_1") (pintype "passive"))
      (node (ref "R139") (pin "1") (pinfunction "1_1") (pintype "passive"))
      (node (ref "R149") (pin "1") (pinfunction "1_1") (pintype "passive"))
    )
    (net (code "35") (name "Net-(Q5-G)") (class "Default")
      (node (ref "D57") (pin "2") (pinfunction "2_2") (pintype "passive"))
      (node (ref "Q5") (pin "1") (pinfunction "G_1") (pintype "passive"))
      (node (ref "R140") (pin "1") (pinfunction "1_1") (pintype "passive"))
      (node (ref "R150") (pin "1") (pinfunction "1_1") (pintype "passive"))
    )
    (net (code "36") (name "Net-(Q6-D)") (class "Default")
      (node (ref "Q6") (pin "1") (pinfunction "D_1") (pintype "passive"))
      (node (ref "R146") (pin "2") (pinfunction "2_2") (pintype "passive"))
    )
    (net (code "37") (name "Net-(Q7-D)") (class "Default")
      (node (ref "Q7") (pin "1") (pinfunction "D_1") (pintype "passive"))
      (node (ref "R147") (pin "2") (pinfunction "2_2") (pintype "passive"))
    )
    (net (code "38") (name "Net-(Q8-D)") (class "Default")
      (node (ref "Q8") (pin "1") (pinfunction "D_1") (pintype "passive"))
      (node (ref "R148") (pin "2") (pinfunction "2_2") (pintype "passive"))
    )
    (net (code "39") (name "Net-(Q9-D)") (class "Default")
      (node (ref "Q9") (pin "1") (pinfunction "D_1") (pintype "passive"))
      (node (ref "R149") (pin "2") (pinfunction "2_2") (pintype "passive"))
    )
    (net (code "40") (name "Net-(Q10-D)") (class "Default")
      (node (ref "Q10") (pin "1") (pinfunction "D_1") (pintype "passive"))
      (node (ref "R150") (pin "2") (pinfunction "2_2") (pintype "passive"))
    )
    (net (code "41") (name "Net-(Q11-D)") (class "Default")
      (node (ref "F3") (pin "2") (pintype "passive"))
      (node (ref "Q11") (pin "2") (pinfunction "D_2") (pintype "passive"))
    )
    (net (code "42") (name "Net-(Q11-G)") (class "Default")
      (node (ref "C184") (pin "2") (pinfunction "2_2") (pintype "passive"))
      (node (ref "Q11") (pin "1") (pinfunction "G_1") (pintype "passive"))
      (node (ref "R156") (pin "2") (pinfunction "2_2") (pintype "passive"))
      (node (ref "R161") (pin "2") (pinfunction "2_2") (pintype "passive"))
    )
    (net (code "43") (name "Net-(Q12-D)") (class "Default")
      (node (ref "F4") (pin "2") (pintype "passive"))
      (node (ref "Q12") (pin "2") (pinfunction "D_2") (pintype "passive"))
    )
    (net (code "44") (name "Net-(Q12-G)") (class "Default")
      (node (ref "C185") (pin "2") (pinfunction "2_2") (pintype "passive"))
      (node (ref "Q12") (pin "1") (pinfunction "G_1") (pintype "passive"))
      (node (ref "R157") (pin "2") (pinfunction "2_2") (pintype "passive"))
      (node (ref "R162") (pin "2") (pinfunction "2_2") (pintype "passive"))
    )
    (net (code "45") (name "Net-(Q13-D)") (class "Default")
      (node (ref "F5") (pin "2") (pintype "passive"))
      (node (ref "Q13") (pin "2") (pinfunction "D_2") (pintype "passive"))
    )
    (net (code "46") (name "Net-(Q13-G)") (class "Default")
      (node (ref "C186") (pin "2") (pinfunction "2_2") (pintype "passive"))
      (node (ref "Q13") (pin "1") (pinfunction "G_1") (pintype "passive"))
      (node (ref "R158") (pin "2") (pinfunction "2_2") (pintype "passive"))
      (node (ref "R163") (pin "2") (pinfunction "2_2") (pintype "passive"))
    )
    (net (code "47") (name "Net-(Q14-D)") (class "Default")
      (node (ref "F6") (pin "2") (pintype "passive"))
      (node (ref "Q14") (pin "2") (pinfunction "D_2") (pintype "passive"))
    )
    (net (code "48") (name "Net-(Q14-G)") (class "Default")
      (node (ref "C187") (pin "2") (pinfunction "2_2") (pintype "passive"))
      (node (ref "Q14") (pin "1") (pinfunction "G_1") (pintype "passive"))
      (node (ref "R159") (pin "2") (pinfunction "2_2") (pintype "passive"))
      (node (ref "R164") (pin "2") (pinfunction "2_2") (pintype "passive"))
    )
    (net (code "49") (name "Net-(Q15-D)") (class "Default")
      (node (ref "F7") (pin "2") (pintype "passive"))
      (node (ref "Q15") (pin "2") (pinfunction "D_2") (pintype "passive"))
    )
    (net (code "50") (name "Net-(Q15-G)") (class "Default")
      (node (ref "C188") (pin "2") (pinfunction "2_2") (pintype "passive"))
      (node (ref "Q15") (pin "1") (pinfunction "G_1") (pintype "passive"))
      (node (ref "R160") (pin "2") (pinfunction "2_2") (pintype "passive"))
      (node (ref "R165") (pin "2") (pinfunction "2_2") (pintype "passive"))
    )
    (net (code "51") (name "Net-(Q16-G)") (class "Default")
      (node (ref "D63") (pin "2") (pinfunction "2_2") (pintype "passive"))
      (node (ref "Q16") (pin "1") (pinfunction "G_1") (pintype "passive"))
      (node (ref "R171") (pin "1") (pinfunction "1_1") (pintype "passive"))
      (node (ref "R181") (pin "1") (pinfunction "1_1") (pintype "passive"))
    )
    (net (code "52") (name "Net-(Q17-G)") (class "Default")
      (node (ref "D64") (pin "2") (pinfunction "2_2") (pintype "passive"))
      (node (ref "Q17") (pin "1") (pinfunction "G_1") (pintype "passive"))
      (node (ref "R172") (pin "1") (pinfunction "1_1") (pintype "passive"))
      (node (ref "R182") (pin "1") (pinfunction "1_1") (pintype "passive"))
    )
    (net (code "53") (name "Net-(Q18-G)") (class "Default")
      (node (ref "D65") (pin "2") (pinfunction "2_2") (pintype "passive"))
      (node (ref "Q18") (pin "1") (pinfunction "G_1") (pintype "passive"))
      (node (ref "R173") (pin "1") (pinfunction "1_1") (pintype "passive"))
      (node (ref "R183") (pin "1") (pinfunction "1_1") (pintype "passive"))
    )
    (net (code "54") (name "Net-(Q19-G)") (class "Default")
      (node (ref "D66") (pin "2") (pinfunction "2_2") (pintype "passive"))
      (node (ref "Q19") (pin "1") (pinfunction "G_1") (pintype "passive"))
      (node (ref "R174") (pin "1") (pinfunction "1_1") (pintype "passive"))
      (node (ref "R184") (pin "1") (pinfunction "1_1") (pintype "passive"))
    )
    (net (code "55") (name "Net-(Q20-G)") (class "Default")
      (node (ref "D67") (pin "2") (pinfunction "2_2") (pintype "passive"))
      (node (ref "Q20") (pin "1") (pinfunction "G_1") (pintype "passive"))
      (node (ref "R175") (pin "1") (pinfunction "1_1") (pintype "passive"))
      (node (ref "R185") (pin "1") (pinfunction "1_1") (pintype "passive"))
    )
    (net (code "56") (name "Net-(Q21-D)") (class "Default")
      (node (ref "Q21") (pin "1") (pinfunction "D_1") (pintype "passive"))
      (node (ref "R181") (pin "2") (pinfunction "2_2") (pintype "passive"))
    )
    (net (code "57") (name "Net-(Q22-D)") (class "Default")
      (node (ref "Q22") (pin "1") (pinfunction "D_1") (pintype "passive"))
      (node (ref "R182") (pin "2") (pinfunction "2_2") (pintype "passive"))
    )
    (net (code "58") (name "Net-(Q23-D)") (class "Default")
      (node (ref "Q23") (pin "1") (pinfunction "D_1") (pintype "passive"))
      (node (ref "R183") (pin "2") (pinfunction "2_2") (pintype "passive"))
    )
    (net (code "59") (name "Net-(Q24-D)") (class "Default")
      (node (ref "Q24") (pin "1") (pinfunction "D_1") (pintype "passive"))
      (node (ref "R184") (pin "2") (pinfunction "2_2") (pintype "passive"))
    )
    (net (code "60") (name "Net-(Q25-D)") (class "Default")
      (node (ref "Q25") (pin "1") (pinfunction "D_1") (pintype "passive"))
      (node (ref "R185") (pin "2") (pinfunction "2_2") (pintype "passive"))
    )
    (net (code "61") (name "Net-(Q26-D)") (class "Default")
      (node (ref "F8") (pin "2") (pintype "passive"))
      (node (ref "Q26") (pin "2") (pinfunction "D_2") (pintype "passive"))
    )
    (net (code "62") (name "Net-(Q26-G)") (class "Default")
      (node (ref "C194") (pin "2") (pinfunction "2_2") (pintype "passive"))
      (node (ref "Q26") (pin "1") (pinfunction "G_1") (pintype "passive"))
      (node (ref "R191") (pin "2") (pinfunction "2_2") (pintype "passive"))
      (node (ref "R196") (pin "2") (pinfunction "2_2") (pintype "passive"))
    )
    (net (code "63") (name "Net-(Q27-D)") (class "Default")
      (node (ref "F9") (pin "2") (pintype "passive"))
      (node (ref "Q27") (pin "2") (pinfunction "D_2") (pintype "passive"))
    )
    (net (code "64") (name "Net-(Q27-G)") (class "Default")
      (node (ref "C195") (pin "2") (pinfunction "2_2") (pintype "passive"))
      (node (ref "Q27") (pin "1") (pinfunction "G_1") (pintype "passive"))
      (node (ref "R192") (pin "2") (pinfunction "2_2") (pintype "passive"))
      (node (ref "R197") (pin "2") (pinfunction "2_2") (pintype "passive"))
    )
    (net (code "65") (name "Net-(Q28-D)") (class "Default")
      (node (ref "F10") (pin "2") (pintype "passive"))
      (node (ref "Q28") (pin "2") (pinfunction "D_2") (pintype "passive"))
    )
    (net (code "66") (name "Net-(Q28-G)") (class "Default")
      (node (ref "C196") (pin "2") (pinfunction "2_2") (pintype "passive"))
      (node (ref "Q28") (pin "1") (pinfunction "G_1") (pintype "passive"))
      (node (ref "R193") (pin "2") (pinfunction "2_2") (pintype "passive"))
      (node (ref "R198") (pin "2") (pinfunction "2_2") (pintype "passive"))
    )
    (net (code "67") (name "Net-(Q29-D)") (class "Default")
      (node (ref "F11") (pin "2") (pintype "passive"))
      (node (ref "Q29") (pin "2") (pinfunction "D_2") (pintype "passive"))
    )
    (net (code "68") (name "Net-(Q29-G)") (class "Default")
      (node (ref "C197") (pin "2") (pinfunction "2_2") (pintype "passive"))
      (node (ref "Q29") (pin "1") (pinfunction "G_1") (pintype "passive"))
      (node (ref "R194") (pin "2") (pinfunction "2_2") (pintype "passive"))
      (node (ref "R199") (pin "2") (pinfunction "2_2") (pintype "passive"))
    )
    (net (code "69") (name "Net-(Q30-D)") (class "Default")
      (node (ref "F12") (pin "2") (pintype "passive"))
      (node (ref "Q30") (pin "2") (pinfunction "D_2") (pintype "passive"))
    )
    (net (code "70") (name "Net-(Q30-G)") (class "Default")
      (node (ref "C198") (pin "2") (pinfunction "2_2") (pintype "passive"))
      (node (ref "Q30") (pin "1") (pinfunction "G_1") (pintype "passive"))
      (node (ref "R195") (pin "2") (pinfunction "2_2") (pintype "passive"))
      (node (ref "R200") (pin "2") (pinfunction "2_2") (pintype "passive"))
    )
    (net (code "71") (name "Net-(Q31-G)") (class "Default")
      (node (ref "D73") (pin "2") (pinfunction "2_2") (pintype "passive"))
      (node (ref "Q31") (pin "1") (pinfunction "G_1") (pintype "passive"))
      (node (ref "R206") (pin "1") (pinfunction "1_1") (pintype "passive"))
      (node (ref "R216") (pin "1") (pinfunction "1_1") (pintype "passive"))
    )
    (net (code "72") (name "Net-(Q32-G)") (class "Default")
      (node (ref "D74") (pin "2") (pinfunction "2_2") (pintype "passive"))
      (node (ref "Q32") (pin "1") (pinfunction "G_1") (pintype "passive"))
      (node (ref "R207") (pin "1") (pinfunction "1_1") (pintype "passive"))
      (node (ref "R217") (pin "1") (pinfunction "1_1") (pintype "passive"))
    )
    (net (code "73") (name "Net-(Q33-G)") (class "Default")
      (node (ref "D75") (pin "2") (pinfunction "2_2") (pintype "passive"))
      (node (ref "Q33") (pin "1") (pinfunction "G_1") (pintype "passive"))
      (node (ref "R208") (pin "1") (pinfunction "1_1") (pintype "passive"))
      (node (ref "R218") (pin "1") (pinfunction "1_1") (pintype "passive"))
    )
    (net (code "74") (name "Net-(Q34-G)") (class "Default")
      (node (ref "D76") (pin "2") (pinfunction "2_2") (pintype "passive"))
      (node (ref "Q34") (pin "1") (pinfunction "G_1") (pintype "passive"))
      (node (ref "R209") (pin "1") (pinfunction "1_1") (pintype "passive"))
      (node (ref "R219") (pin "1") (pinfunction "1_1") (pintype "passive"))
    )
    (net (code "75") (name "Net-(Q35-G)") (class "Default")
      (node (ref "D77") (pin "2") (pinfunction "2_2") (pintype "passive"))
      (node (ref "Q35") (pin "1") (pinfunction "G_1") (pintype "passive"))
      (node (ref "R210") (pin "1") (pinfunction "1_1") (pintype "passive"))
      (node (ref "R220") (pin "1") (pinfunction "1_1") (pintype "passive"))
    )
    (net (code "76") (name "Net-(Q36-D)") (class "Default")
      (node (ref "Q36") (pin "1") (pinfunction "D_1") (pintype "passive"))
      (node (ref "R216") (pin "2") (pinfunction "2_2") (pintype "passive"))
    )
    (net (code "77") (name "Net-(Q37-D)") (class "Default")
      (node (ref "Q37") (pin "1") (pinfunction "D_1") (pintype "passive"))
      (node (ref "R217") (pin "2") (pinfunction "2_2") (pintype "passive"))
    )
    (net (code "78") (name "Net-(Q38-D)") (class "Default")
      (node (ref "Q38") (pin "1") (pinfunction "D_1") (pintype "passive"))
      (node (ref "R218") (pin "2") (pinfunction "2_2") (pintype "passive"))
    )
    (net (code "79") (name "Net-(Q39-D)") (class "Default")
      (node (ref "Q39") (pin "1") (pinfunction "D_1") (pintype "passive"))
      (node (ref "R219") (pin "2") (pinfunction "2_2") (pintype "passive"))
    )
    (net (code "80") (name "Net-(Q40-D)") (class "Default")
      (node (ref "Q40") (pin "1") (pinfunction "D_1") (pintype "passive"))
      (node (ref "R220") (pin "2") (pinfunction "2_2") (pintype "passive"))
    )
    (net (code "81") (name "Net-(Q41-D)") (class "Default")
      (node (ref "F13") (pin "2") (pintype "passive"))
      (node (ref "Q41") (pin "2") (pinfunction "D_2") (pintype "passive"))
    )
    (net (code "82") (name "Net-(Q41-G)") (class "Default")
      (node (ref "C204") (pin "2") (pinfunction "2_2") (pintype "passive"))
      (node (ref "Q41") (pin "1") (pinfunction "G_1") (pintype "passive"))
      (node (ref "R226") (pin "2") (pinfunction "2_2") (pintype "passive"))
      (node (ref "R231") (pin "2") (pinfunction "2_2") (pintype "passive"))
    )
    (net (code "83") (name "Net-(Q42-D)") (class "Default")
      (node (ref "F14") (pin "2") (pintype "passive"))
      (node (ref "Q42") (pin "2") (pinfunction "D_2") (pintype "passive"))
    )
    (net (code "84") (name "Net-(Q42-G)") (class "Default")
      (node (ref "C205") (pin "2") (pinfunction "2_2") (pintype "passive"))
      (node (ref "Q42") (pin "1") (pinfunction "G_1") (pintype "passive"))
      (node (ref "R227") (pin "2") (pinfunction "2_2") (pintype "passive"))
      (node (ref "R232") (pin "2") (pinfunction "2_2") (pintype "passive"))
    )
    (net (code "85") (name "Net-(Q43-D)") (class "Default")
      (node (ref "F15") (pin "2") (pintype "passive"))
      (node (ref "Q43") (pin "2") (pinfunction "D_2") (pintype "passive"))
    )
    (net (code "86") (name "Net-(Q43-G)") (class "Default")
      (node (ref "C206") (pin "2") (pinfunction "2_2") (pintype "passive"))
      (node (ref "Q43") (pin "1") (pinfunction "G_1") (pintype "passive"))
      (node (ref "R228") (pin "2") (pinfunction "2_2") (pintype "passive"))
      (node (ref "R233") (pin "2") (pinfunction "2_2") (pintype "passive"))
    )
    (net (code "87") (name "Net-(Q44-D)") (class "Default")
      (node (ref "F16") (pin "2") (pintype "passive"))
      (node (ref "Q44") (pin "2") (pinfunction "D_2") (pintype "passive"))
    )
    (net (code "88") (name "Net-(Q44-G)") (class "Default")
      (node (ref "C207") (pin "2") (pinfunction "2_2") (pintype "passive"))
      (node (ref "Q44") (pin "1") (pinfunction "G_1") (pintype "passive"))
      (node (ref "R229") (pin "2") (pinfunction "2_2") (pintype "passive"))
      (node (ref "R234") (pin "2") (pinfunction "2_2") (pintype "passive"))
    )
    (net (code "89") (name "Net-(Q45-D)") (class "Default")
      (node (ref "F17") (pin "2") (pintype "passive"))
      (node (ref "Q45") (pin "2") (pinfunction "D_2") (pintype "passive"))
    )
    (net (code "90") (name "Net-(Q45-G)") (class "Default")
      (node (ref "C208") (pin "2") (pinfunction "2_2") (pintype "passive"))
      (node (ref "Q45") (pin "1") (pinfunction "G_1") (pintype "passive"))
      (node (ref "R230") (pin "2") (pinfunction "2_2") (pintype "passive"))
      (node (ref "R235") (pin "2") (pinfunction "2_2") (pintype "passive"))
    )
    (net (code "91") (name "PF1+") (class "Default")
      (node (ref "C179") (pin "2") (pinfunction "2_2") (pintype "passive"))
      (node (ref "Q6") (pin "2") (pinfunction "G_2") (pintype "passive"))
      (node (ref "R151") (pin "2") (pinfunction "2_2") (pintype "passive"))
    )
    (net (code "92") (name "PF1-") (class "Default")
      (node (ref "R156") (pin "1") (pinfunction "1_1") (pintype "passive"))
      (node (ref "R166") (pin "1") (pinfunction "1_1") (pintype "passive"))
    )
    (net (code "93") (name "PF2+") (class "Default")
      (node (ref "C180") (pin "2") (pinfunction "2_2") (pintype "passive"))
      (node (ref "Q7") (pin "2") (pinfunction "G_2") (pintype "passive"))
      (node (ref "R152") (pin "2") (pinfunction "2_2") (pintype "passive"))
    )
    (net (code "94") (name "PF2-") (class "Default")
      (node (ref "R157") (pin "1") (pinfunction "1_1") (pintype "passive"))
      (node (ref "R167") (pin "1") (pinfunction "1_1") (pintype "passive"))
    )
    (net (code "95") (name "PF3+") (class "Default")
      (node (ref "C181") (pin "2") (pinfunction "2_2") (pintype "passive"))
      (node (ref "Q8") (pin "2") (pinfunction "G_2") (pintype "passive"))
      (node (ref "R153") (pin "2") (pinfunction "2_2") (pintype "passive"))
    )
    (net (code "96") (name "PF3-") (class "Default")
      (node (ref "R158") (pin "1") (pinfunction "1_1") (pintype "passive"))
      (node (ref "R168") (pin "1") (pinfunction "1_1") (pintype "passive"))
    )
    (net (code "97") (name "PF4+") (class "Default")
      (node (ref "C182") (pin "2") (pinfunction "2_2") (pintype "passive"))
      (node (ref "Q9") (pin "2") (pinfunction "G_2") (pintype "passive"))
      (node (ref "R154") (pin "2") (pinfunction "2_2") (pintype "passive"))
    )
    (net (code "98") (name "PF4-") (class "Default")
      (node (ref "R159") (pin "1") (pinfunction "1_1") (pintype "passive"))
      (node (ref "R169") (pin "1") (pinfunction "1_1") (pintype "passive"))
    )
    (net (code "99") (name "PF5+") (class "Default")
      (node (ref "C183") (pin "2") (pinfunction "2_2") (pintype "passive"))
      (node (ref "Q10") (pin "2") (pinfunction "G_2") (pintype "passive"))
      (node (ref "R155") (pin "2") (pinfunction "2_2") (pintype "passive"))
    )
    (net (code "100") (name "PF5-") (class "Default")
      (node (ref "R160") (pin "1") (pinfunction "1_1") (pintype "passive"))
      (node (ref "R170") (pin "1") (pinfunction "1_1") (pintype "passive"))
    )
    (net (code "101") (name "PF6+") (class "Default")
      (node (ref "C189") (pin "2") (pinfunction "2_2") (pintype "passive"))
      (node (ref "Q21") (pin "2") (pinfunction "G_2") (pintype "passive"))
      (node (ref "R186") (pin "2") (pinfunction "2_2") (pintype "passive"))
    )
    (net (code "102") (name "PF6-") (class "Default")
      (node (ref "R191") (pin "1") (pinfunction "1_1") (pintype "passive"))
      (node (ref "R201") (pin "1") (pinfunction "1_1") (pintype "passive"))
    )
    (net (code "103") (name "PF7+") (class "Default")
      (node (ref "C190") (pin "2") (pinfunction "2_2") (pintype "passive"))
      (node (ref "Q22") (pin "2") (pinfunction "G_2") (pintype "passive"))
      (node (ref "R187") (pin "2") (pinfunction "2_2") (pintype "passive"))
    )
    (net (code "104") (name "PF7-") (class "Default")
      (node (ref "R192") (pin "1") (pinfunction "1_1") (pintype "passive"))
      (node (ref "R202") (pin "1") (pinfunction "1_1") (pintype "passive"))
    )
    (net (code "105") (name "PF8+") (class "Default")
      (node (ref "C191") (pin "2") (pinfunction "2_2") (pintype "passive"))
      (node (ref "Q23") (pin "2") (pinfunction "G_2") (pintype "passive"))
      (node (ref "R188") (pin "2") (pinfunction "2_2") (pintype "passive"))
    )
    (net (code "106") (name "PF8-") (class "Default")
      (node (ref "R193") (pin "1") (pinfunction "1_1") (pintype "passive"))
      (node (ref "R203") (pin "1") (pinfunction "1_1") (pintype "passive"))
    )
    (net (code "107") (name "PF9+") (class "Default")
      (node (ref "C192") (pin "2") (pinfunction "2_2") (pintype "passive"))
      (node (ref "Q24") (pin "2") (pinfunction "G_2") (pintype "passive"))
      (node (ref "R189") (pin "2") (pinfunction "2_2") (pintype "passive"))
    )
    (net (code "108") (name "PF9-") (class "Default")
      (node (ref "R194") (pin "1") (pinfunction "1_1") (pintype "passive"))
      (node (ref "R204") (pin "1") (pinfunction "1_1") (pintype "passive"))
    )
    (net (code "109") (name "PF10+") (class "Default")
      (node (ref "C193") (pin "2") (pinfunction "2_2") (pintype "passive"))
      (node (ref "Q25") (pin "2") (pinfunction "G_2") (pintype "passive"))
      (node (ref "R190") (pin "2") (pinfunction "2_2") (pintype "passive"))
    )
    (net (code "110") (name "PF10-") (class "Default")
      (node (ref "R195") (pin "1") (pinfunction "1_1") (pintype "passive"))
      (node (ref "R205") (pin "1") (pinfunction "1_1") (pintype "passive"))
    )
    (net (code "111") (name "PF11+") (class "Default")
      (node (ref "C199") (pin "2") (pinfunction "2_2") (pintype "passive"))
      (node (ref "Q36") (pin "2") (pinfunction "G_2") (pintype "passive"))
      (node (ref "R221") (pin "2") (pinfunction "2_2") (pintype "passive"))
    )
    (net (code "112") (name "PF11-") (class "Default")
      (node (ref "R226") (pin "1") (pinfunction "1_1") (pintype "passive"))
      (node (ref "R236") (pin "1") (pinfunction "1_1") (pintype "passive"))
    )
    (net (code "113") (name "PF12+") (class "Default")
      (node (ref "C200") (pin "2") (pinfunction "2_2") (pintype "passive"))
      (node (ref "Q37") (pin "2") (pinfunction "G_2") (pintype "passive"))
      (node (ref "R222") (pin "2") (pinfunction "2_2") (pintype "passive"))
    )
    (net (code "114") (name "PF12-") (class "Default")
      (node (ref "R227") (pin "1") (pinfunction "1_1") (pintype "passive"))
      (node (ref "R237") (pin "1") (pinfunction "1_1") (pintype "passive"))
    )
    (net (code "115") (name "PF13+") (class "Default")
      (node (ref "C201") (pin "2") (pinfunction "2_2") (pintype "passive"))
      (node (ref "Q38") (pin "2") (pinfunction "G_2") (pintype "passive"))
      (node (ref "R223") (pin "2") (pinfunction "2_2") (pintype "passive"))
    )
    (net (code "116") (name "PF13-") (class "Default")
      (node (ref "R228") (pin "1") (pinfunction "1_1") (pintype "passive"))
      (node (ref "R238") (pin "1") (pinfunction "1_1") (pintype "passive"))
    )
    (net (code "117") (name "PF14+") (class "Default")
      (node (ref "C202") (pin "2") (pinfunction "2_2") (pintype "passive"))
      (node (ref "Q39") (pin "2") (pinfunction "G_2") (pintype "passive"))
      (node (ref "R224") (pin "2") (pinfunction "2_2") (pintype "passive"))
    )
    (net (code "118") (name "PF14-") (class "Default")
      (node (ref "R229") (pin "1") (pinfunction "1_1") (pintype "passive"))
      (node (ref "R239") (pin "1") (pinfunction "1_1") (pintype "passive"))
    )
    (net (code "119") (name "PF15+") (class "Default")
      (node (ref "C203") (pin "2") (pinfunction "2_2") (pintype "passive"))
      (node (ref "Q40") (pin "2") (pinfunction "G_2") (pintype "passive"))
      (node (ref "R225") (pin "2") (pinfunction "2_2") (pintype "passive"))
    )
    (net (code "120") (name "PF15-") (class "Default")
      (node (ref "R230") (pin "1") (pinfunction "1_1") (pintype "passive"))
      (node (ref "R240") (pin "1") (pinfunction "1_1") (pintype "passive"))
    )
    (net (code "121") (name "PGND") (class "Default")
      (node (ref "C179") (pin "1") (pinfunction "1_1") (pintype "passive"))
      (node (ref "C180") (pin "1") (pinfunction "1_1") (pintype "passive"))
      (node (ref "C181") (pin "1") (pinfunction "1_1") (pintype "passive"))
      (node (ref "C182") (pin "1") (pinfunction "1_1") (pintype "passive"))
      (node (ref "C183") (pin "1") (pinfunction "1_1") (pintype "passive"))
      (node (ref "C184") (pin "1") (pinfunction "1_1") (pintype "passive"))
      (node (ref "C185") (pin "1") (pinfunction "1_1") (pintype "passive"))
      (node (ref "C186") (pin "1") (pinfunction "1_1") (pintype "passive"))
      (node (ref "C187") (pin "1") (pinfunction "1_1") (pintype "passive"))
      (node (ref "C188") (pin "1") (pinfunction "1_1") (pintype "passive"))
      (node (ref "C189") (pin "1") (pinfunction "1_1") (pintype "passive"))
      (node (ref "C190") (pin "1") (pinfunction "1_1") (pintype "passive"))
      (node (ref "C191") (pin "1") (pinfunction "1_1") (pintype "passive"))
      (node (ref "C192") (pin "1") (pinfunction "1_1") (pintype "passive"))
      (node (ref "C193") (pin "1") (pinfunction "1_1") (pintype "passive"))
      (node (ref "C194") (pin "1") (pinfunction "1_1") (pintype "passive"))
      (node (ref "C195") (pin "1") (pinfunction "1_1") (pintype "passive"))
      (node (ref "C196") (pin "1") (pinfunction "1_1") (pintype "passive"))
      (node (ref "C197") (pin "1") (pinfunction "1_1") (pintype "passive"))
      (node (ref "C198") (pin "1") (pinfunction "1_1") (pintype "passive"))
      (node (ref "C199") (pin "1") (pinfunction "1_1") (pintype "passive"))
      (node (ref "C200") (pin "1") (pinfunction "1_1") (pintype "passive"))
      (node (ref "C201") (pin "1") (pinfunction "1_1") (pintype "passive"))
      (node (ref "C202") (pin "1") (pinfunction "1_1") (pintype "passive"))
      (node (ref "C203") (pin "1") (pinfunction "1_1") (pintype "passive"))
      (node (ref "C204") (pin "1") (pinfunction "1_1") (pintype "passive"))
      (node (ref "C205") (pin "1") (pinfunction "1_1") (pintype "passive"))
      (node (ref "C206") (pin "1") (pinfunction "1_1") (pintype "passive"))
      (node (ref "C207") (pin "1") (pinfunction "1_1") (pintype "passive"))
      (node (ref "C208") (pin "1") (pinfunction "1_1") (pintype "passive"))
      (node (ref "Q10") (pin "3") (pinfunction "S_3") (pintype "passive"))
      (node (ref "Q11") (pin "3") (pinfunction "S_3") (pintype "passive"))
      (node (ref "Q12") (pin "3") (pinfunction "S_3") (pintype "passive"))
      (node (ref "Q13") (pin "3") (pinfunction "S_3") (pintype "passive"))
      (node (ref "Q14") (pin "3") (pinfunction "S_3") (pintype "passive"))
      (node (ref "Q15") (pin "3") (pinfunction "S_3") (pintype "passive"))
      (node (ref "Q21") (pin "3") (pinfunction "S_3") (pintype "passive"))
      (node (ref "Q22") (pin "3") (pinfunction "S_3") (pintype "passive"))
      (node (ref "Q23") (pin "3") (pinfunction "S_3") (pintype "passive"))
      (node (ref "Q24") (pin "3") (pinfunction "S_3") (pintype "passive"))
      (node (ref "Q25") (pin "3") (pinfunction "S_3") (pintype "passive"))
      (node (ref "Q26") (pin "3") (pinfunction "S_3") (pintype "passive"))
      (node (ref "Q27") (pin "3") (pinfunction "S_3") (pintype "passive"))
      (node (ref "Q28") (pin "3") (pinfunction "S_3") (pintype "passive"))
      (node (ref "Q29") (pin "3") (pinfunction "S_3") (pintype "passive"))
      (node (ref "Q30") (pin "3") (pinfunction "S_3") (pintype "passive"))
      (node (ref "Q36") (pin "3") (pinfunction "S_3") (pintype "passive"))
      (node (ref "Q37") (pin "3") (pinfunction "S_3") (pintype "passive"))
      (node (ref "Q38") (pin "3") (pinfunction "S_3") (pintype "passive"))
      (node (ref "Q39") (pin "3") (pinfunction "S_3") (pintype "passive"))
      (node (ref "Q40") (pin "3") (pinfunction "S_3") (pintype "passive"))
      (node (ref "Q41") (pin "3") (pinfunction "S_3") (pintype "passive"))
      (node (ref "Q42") (pin "3") (pinfunction "S_3") (pintype "passive"))
      (node (ref "Q43") (pin "3") (pinfunction "S_3") (pintype "passive"))
      (node (ref "Q44") (pin "3") (pinfunction "S_3") (pintype "passive"))
      (node (ref "Q45") (pin "3") (pinfunction "S_3") (pintype "passive"))
      (node (ref "Q6") (pin "3") (pinfunction "S_3") (pintype "passive"))
      (node (ref "Q7") (pin "3") (pinfunction "S_3") (pintype "passive"))
      (node (ref "Q8") (pin "3") (pinfunction "S_3") (pintype "passive"))
      (node (ref "Q9") (pin "3") (pinfunction "S_3") (pintype "passive"))
      (node (ref "R151") (pin "1") (pinfunction "1_1") (pintype "passive"))
      (node (ref "R152") (pin "1") (pinfunction "1_1") (pintype "passive"))
      (node (ref "R153") (pin "1") (pinfunction "1_1") (pintype "passive"))
      (node (ref "R154") (pin "1") (pinfunction "1_1") (pintype "passive"))
      (node (ref "R155") (pin "1") (pinfunction "1_1") (pintype "passive"))
      (node (ref "R161") (pin "1") (pinfunction "1_1") (pintype "passive"))
      (node (ref "R162") (pin "1") (pinfunction "1_1") (pintype "passive"))
      (node (ref "R163") (pin "1") (pinfunction "1_1") (pintype "passive"))
      (node (ref "R164") (pin "1") (pinfunction "1_1") (pintype "passive"))
      (node (ref "R165") (pin "1") (pinfunction "1_1") (pintype "passive"))
      (node (ref "R166") (pin "2") (pinfunction "2_2") (pintype "passive"))
      (node (ref "R167") (pin "2") (pinfunction "2_2") (pintype "passive"))
      (node (ref "R168") (pin "2") (pinfunction "2_2") (pintype "passive"))
      (node (ref "R169") (pin "2") (pinfunction "2_2") (pintype "passive"))
      (node (ref "R170") (pin "2") (pinfunction "2_2") (pintype "passive"))
      (node (ref "R186") (pin "1") (pinfunction "1_1") (pintype "passive"))
      (node (ref "R187") (pin "1") (pinfunction "1_1") (pintype "passive"))
      (node (ref "R188") (pin "1") (pinfunction "1_1") (pintype "passive"))
      (node (ref "R189") (pin "1") (pinfunction "1_1") (pintype "passive"))
      (node (ref "R190") (pin "1") (pinfunction "1_1") (pintype "passive"))
      (node (ref "R196") (pin "1") (pinfunction "1_1") (pintype "passive"))
      (node (ref "R197") (pin "1") (pinfunction "1_1") (pintype "passive"))
      (node (ref "R198") (pin "1") (pinfunction "1_1") (pintype "passive"))
      (node (ref "R199") (pin "1") (pinfunction "1_1") (pintype "passive"))
      (node (ref "R200") (pin "1") (pinfunction "1_1") (pintype "passive"))
      (node (ref "R201") (pin "2") (pinfunction "2_2") (pintype "passive"))
      (node (ref "R202") (pin "2") (pinfunction "2_2") (pintype "passive"))
      (node (ref "R203") (pin "2") (pinfunction "2_2") (pintype "passive"))
      (node (ref "R204") (pin "2") (pinfunction "2_2") (pintype "passive"))
      (node (ref "R205") (pin "2") (pinfunction "2_2") (pintype "passive"))
      (node (ref "R221") (pin "1") (pinfunction "1_1") (pintype "passive"))
      (node (ref "R222") (pin "1") (pinfunction "1_1") (pintype "passive"))
      (node (ref "R223") (pin "1") (pinfunction "1_1") (pintype "passive"))
      (node (ref "R224") (pin "1") (pinfunction "1_1") (pintype "passive"))
      (node (ref "R225") (pin "1") (pinfunction "1_1") (pintype "passive"))
      (node (ref "R231") (pin "1") (pinfunction "1_1") (pintype "passive"))
      (node (ref "R232") (pin "1") (pinfunction "1_1") (pintype "passive"))
      (node (ref "R233") (pin "1") (pinfunction "1_1") (pintype "passive"))
      (node (ref "R234") (pin "1") (pinfunction "1_1") (pintype "passive"))
      (node (ref "R235") (pin "1") (pinfunction "1_1") (pintype "passive"))
      (node (ref "R236") (pin "2") (pinfunction "2_2") (pintype "passive"))
      (node (ref "R237") (pin "2") (pinfunction "2_2") (pintype "passive"))
      (node (ref "R238") (pin "2") (pinfunction "2_2") (pintype "passive"))
      (node (ref "R239") (pin "2") (pinfunction "2_2") (pintype "passive"))
      (node (ref "R240") (pin "2") (pinfunction "2_2") (pintype "passive"))
    )
    (net (code "122") (name "PHIGH") (class "Default")
      (node (ref "D53") (pin "1") (pinfunction "1_1") (pintype "passive"))
      (node (ref "D54") (pin "1") (pinfunction "1_1") (pintype "passive"))
      (node (ref "D55") (pin "1") (pinfunction "1_1") (pintype "passive"))
      (node (ref "D56") (pin "1") (pinfunction "1_1") (pintype "passive"))
      (node (ref "D57") (pin "1") (pinfunction "1_1") (pintype "passive"))
      (node (ref "D63") (pin "1") (pinfunction "1_1") (pintype "passive"))
      (node (ref "D64") (pin "1") (pinfunction "1_1") (pintype "passive"))
      (node (ref "D65") (pin "1") (pinfunction "1_1") (pintype "passive"))
      (node (ref "D66") (pin "1") (pinfunction "1_1") (pintype "passive"))
      (node (ref "D67") (pin "1") (pinfunction "1_1") (pintype "passive"))
      (node (ref "D73") (pin "1") (pinfunction "1_1") (pintype "passive"))
      (node (ref "D74") (pin "1") (pinfunction "1_1") (pintype "passive"))
      (node (ref "D75") (pin "1") (pinfunction "1_1") (pintype "passive"))
      (node (ref "D76") (pin "1") (pinfunction "1_1") (pintype "passive"))
      (node (ref "D77") (pin "1") (pinfunction "1_1") (pintype "passive"))
      (node (ref "Q1") (pin "3") (pinfunction "S_3") (pintype "passive"))
      (node (ref "Q16") (pin "3") (pinfunction "S_3") (pintype "passive"))
      (node (ref "Q17") (pin "3") (pinfunction "S_3") (pintype "passive"))
      (node (ref "Q18") (pin "3") (pinfunction "S_3") (pintype "passive"))
      (node (ref "Q19") (pin "3") (pinfunction "S_3") (pintype "passive"))
      (node (ref "Q2") (pin "3") (pinfunction "S_3") (pintype "passive"))
      (node (ref "Q20") (pin "3") (pinfunction "S_3") (pintype "passive"))
      (node (ref "Q3") (pin "3") (pinfunction "S_3") (pintype "passive"))
      (node (ref "Q31") (pin "3") (pinfunction "S_3") (pintype "passive"))
      (node (ref "Q32") (pin "3") (pinfunction "S_3") (pintype "passive"))
      (node (ref "Q33") (pin "3") (pinfunction "S_3") (pintype "passive"))
      (node (ref "Q34") (pin "3") (pinfunction "S_3") (pintype "passive"))
      (node (ref "Q35") (pin "3") (pinfunction "S_3") (pintype "passive"))
      (node (ref "Q4") (pin "3") (pinfunction "S_3") (pintype "passive"))
      (node (ref "Q5") (pin "3") (pinfunction "S_3") (pintype "passive"))
      (node (ref "R136") (pin "2") (pinfunction "2_2") (pintype "passive"))
      (node (ref "R137") (pin "2") (pinfunction "2_2") (pintype "passive"))
      (node (ref "R138") (pin "2") (pinfunction "2_2") (pintype "passive"))
      (node (ref "R139") (pin "2") (pinfunction "2_2") (pintype "passive"))
      (node (ref "R140") (pin "2") (pinfunction "2_2") (pintype "passive"))
      (node (ref "R141") (pin "2") (pinfunction "2_2") (pintype "passive"))
      (node (ref "R142") (pin "2") (pinfunction "2_2") (pintype "passive"))
      (node (ref "R143") (pin "2") (pinfunction "2_2") (pintype "passive"))
      (node (ref "R144") (pin "2") (pinfunction "2_2") (pintype "passive"))
      (node (ref "R145") (pin "2") (pinfunction "2_2") (pintype "passive"))
      (node (ref "R171") (pin "2") (pinfunction "2_2") (pintype "passive"))
      (node (ref "R172") (pin "2") (pinfunction "2_2") (pintype "passive"))
      (node (ref "R173") (pin "2") (pinfunction "2_2") (pintype "passive"))
      (node (ref "R174") (pin "2") (pinfunction "2_2") (pintype "passive"))
      (node (ref "R175") (pin "2") (pinfunction "2_2") (pintype "passive"))
      (node (ref "R176") (pin "2") (pinfunction "2_2") (pintype "passive"))
      (node (ref "R177") (pin "2") (pinfunction "2_2") (pintype "passive"))
      (node (ref "R178") (pin "2") (pinfunction "2_2") (pintype "passive"))
      (node (ref "R179") (pin "2") (pinfunction "2_2") (pintype "passive"))
      (node (ref "R180") (pin "2") (pinfunction "2_2") (pintype "passive"))
      (node (ref "R206") (pin "2") (pinfunction "2_2") (pintype "passive"))
      (node (ref "R207") (pin "2") (pinfunction "2_2") (pintype "passive"))
      (node (ref "R208") (pin "2") (pinfunction "2_2") (pintype "passive"))
      (node (ref "R209") (pin "2") (pinfunction "2_2") (pintype "passive"))
      (node (ref "R210") (pin "2") (pinfunction "2_2") (pintype "passive"))
      (node (ref "R211") (pin "2") (pinfunction "2_2") (pintype "passive"))
      (node (ref "R212") (pin "2") (pinfunction "2_2") (pintype "passive"))
      (node (ref "R213") (pin "2") (pinfunction "2_2") (pintype "passive"))
      (node (ref "R214") (pin "2") (pinfunction "2_2") (pintype "passive"))
      (node (ref "R215") (pin "2") (pinfunction "2_2") (pintype "passive"))
    )
    (net (code "123") (name "PLOW") (class "Default")
      (node (ref "D58") (pin "2") (pinfunction "2_2") (pintype "passive"))
      (node (ref "D59") (pin "2") (pinfunction "2_2") (pintype "passive"))
      (node (ref "D60") (pin "2") (pinfunction "2_2") (pintype "passive"))
      (node (ref "D61") (pin "2") (pinfunction "2_2") (pintype "passive"))
      (node (ref "D62") (pin "2") (pinfunction "2_2") (pintype "passive"))
      (node (ref "D68") (pin "2") (pinfunction "2_2") (pintype "passive"))
      (node (ref "D69") (pin "2") (pinfunction "2_2") (pintype "passive"))
      (node (ref "D70") (pin "2") (pinfunction "2_2") (pintype "passive"))
      (node (ref "D71") (pin "2") (pinfunction "2_2") (pintype "passive"))
      (node (ref "D72") (pin "2") (pinfunction "2_2") (pintype "passive"))
      (node (ref "D78") (pin "2") (pinfunction "2_2") (pintype "passive"))
      (node (ref "D79") (pin "2") (pinfunction "2_2") (pintype "passive"))
      (node (ref "D80") (pin "2") (pinfunction "2_2") (pintype "passive"))
      (node (ref "D81") (pin "2") (pinfunction "2_2") (pintype "passive"))
      (node (ref "D82") (pin "2") (pinfunction "2_2") (pintype "passive"))
    )
  )
)
